# senseBox-MCU_v12.net
KiCad netlist of a schematic drawn in EAGLE
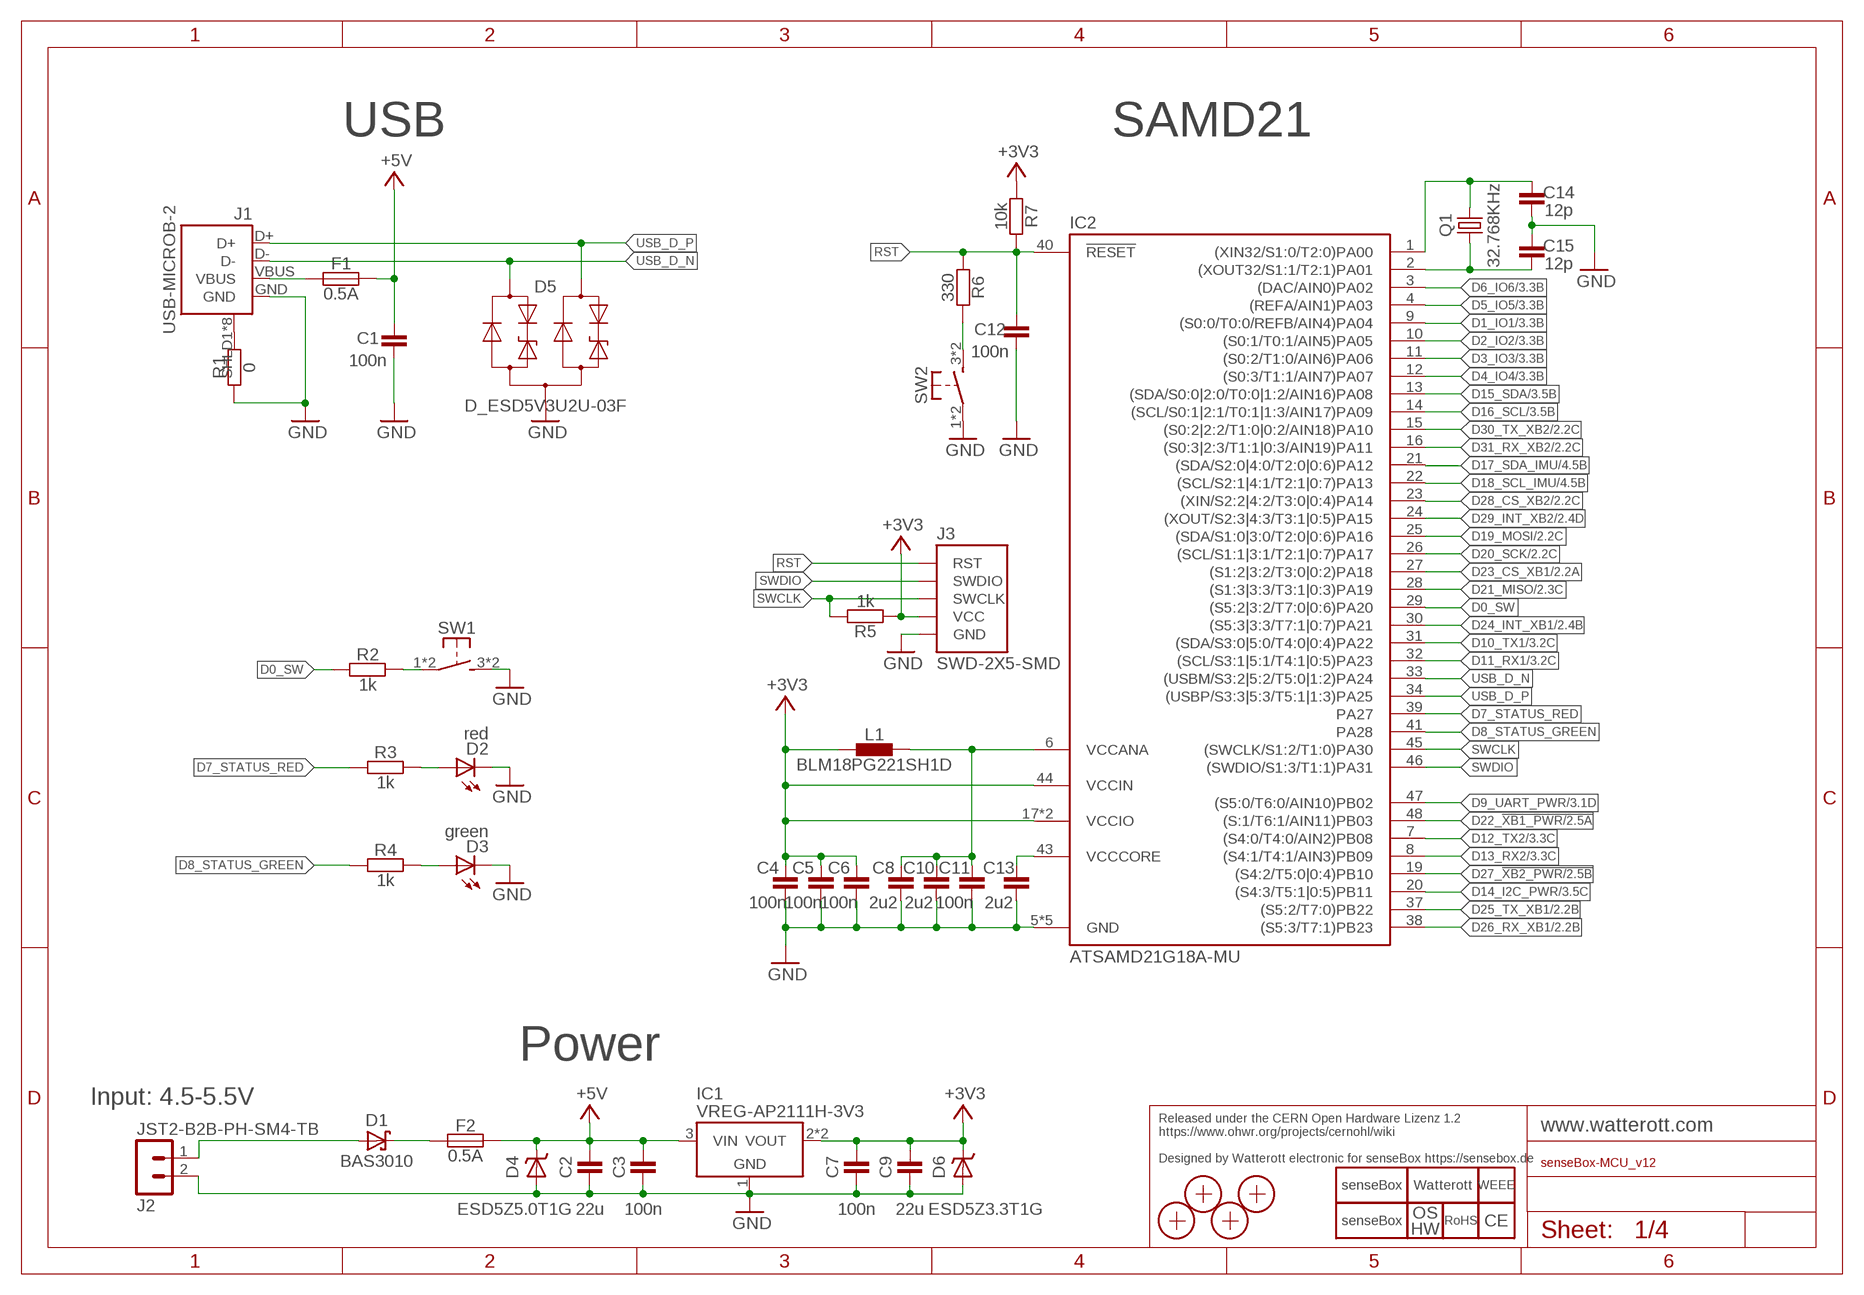
[diagram p0: schematic, sheet 1]
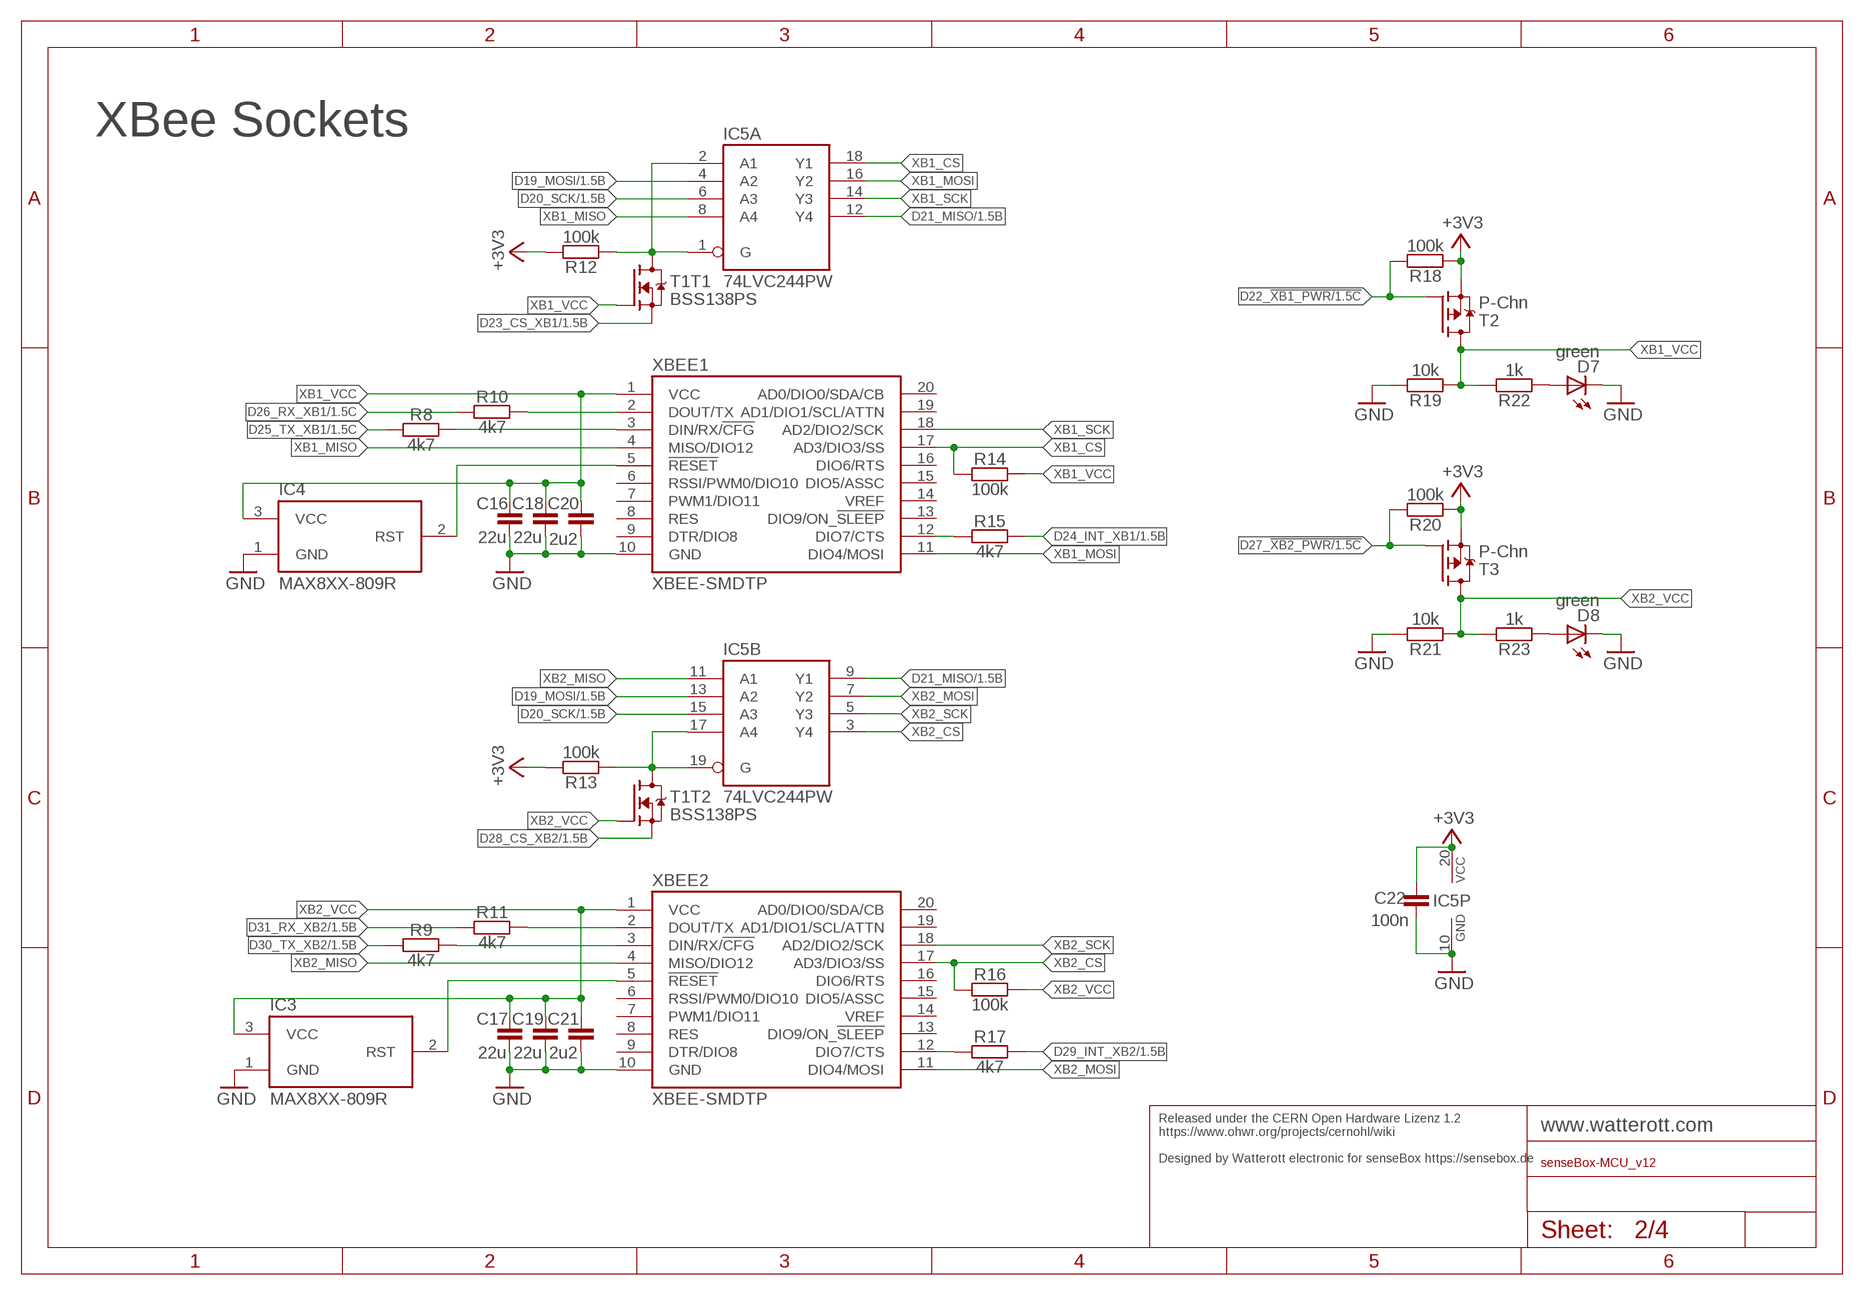
[diagram p1: schematic, sheet 2]
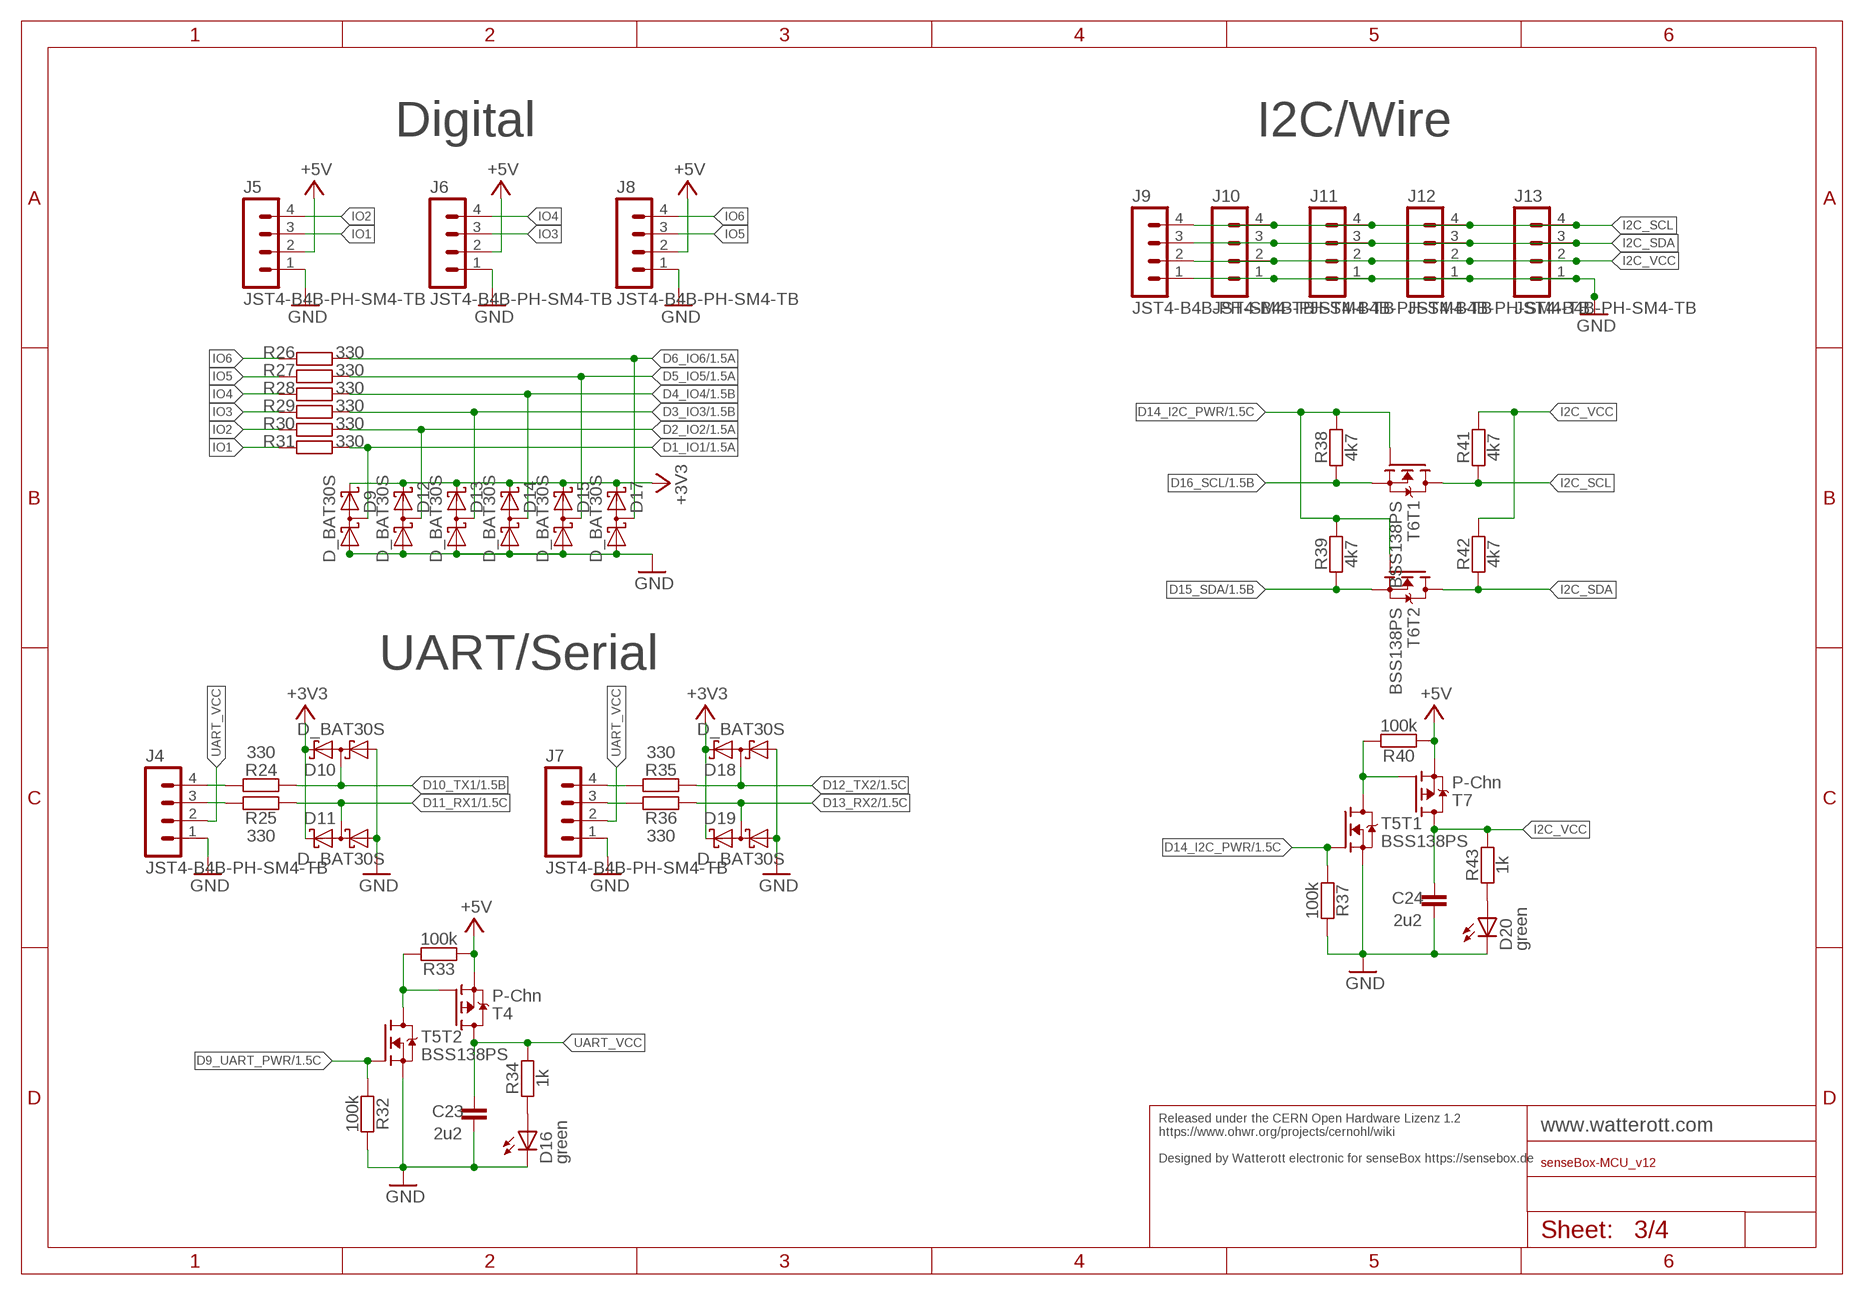
[diagram p2: schematic, sheet 3]
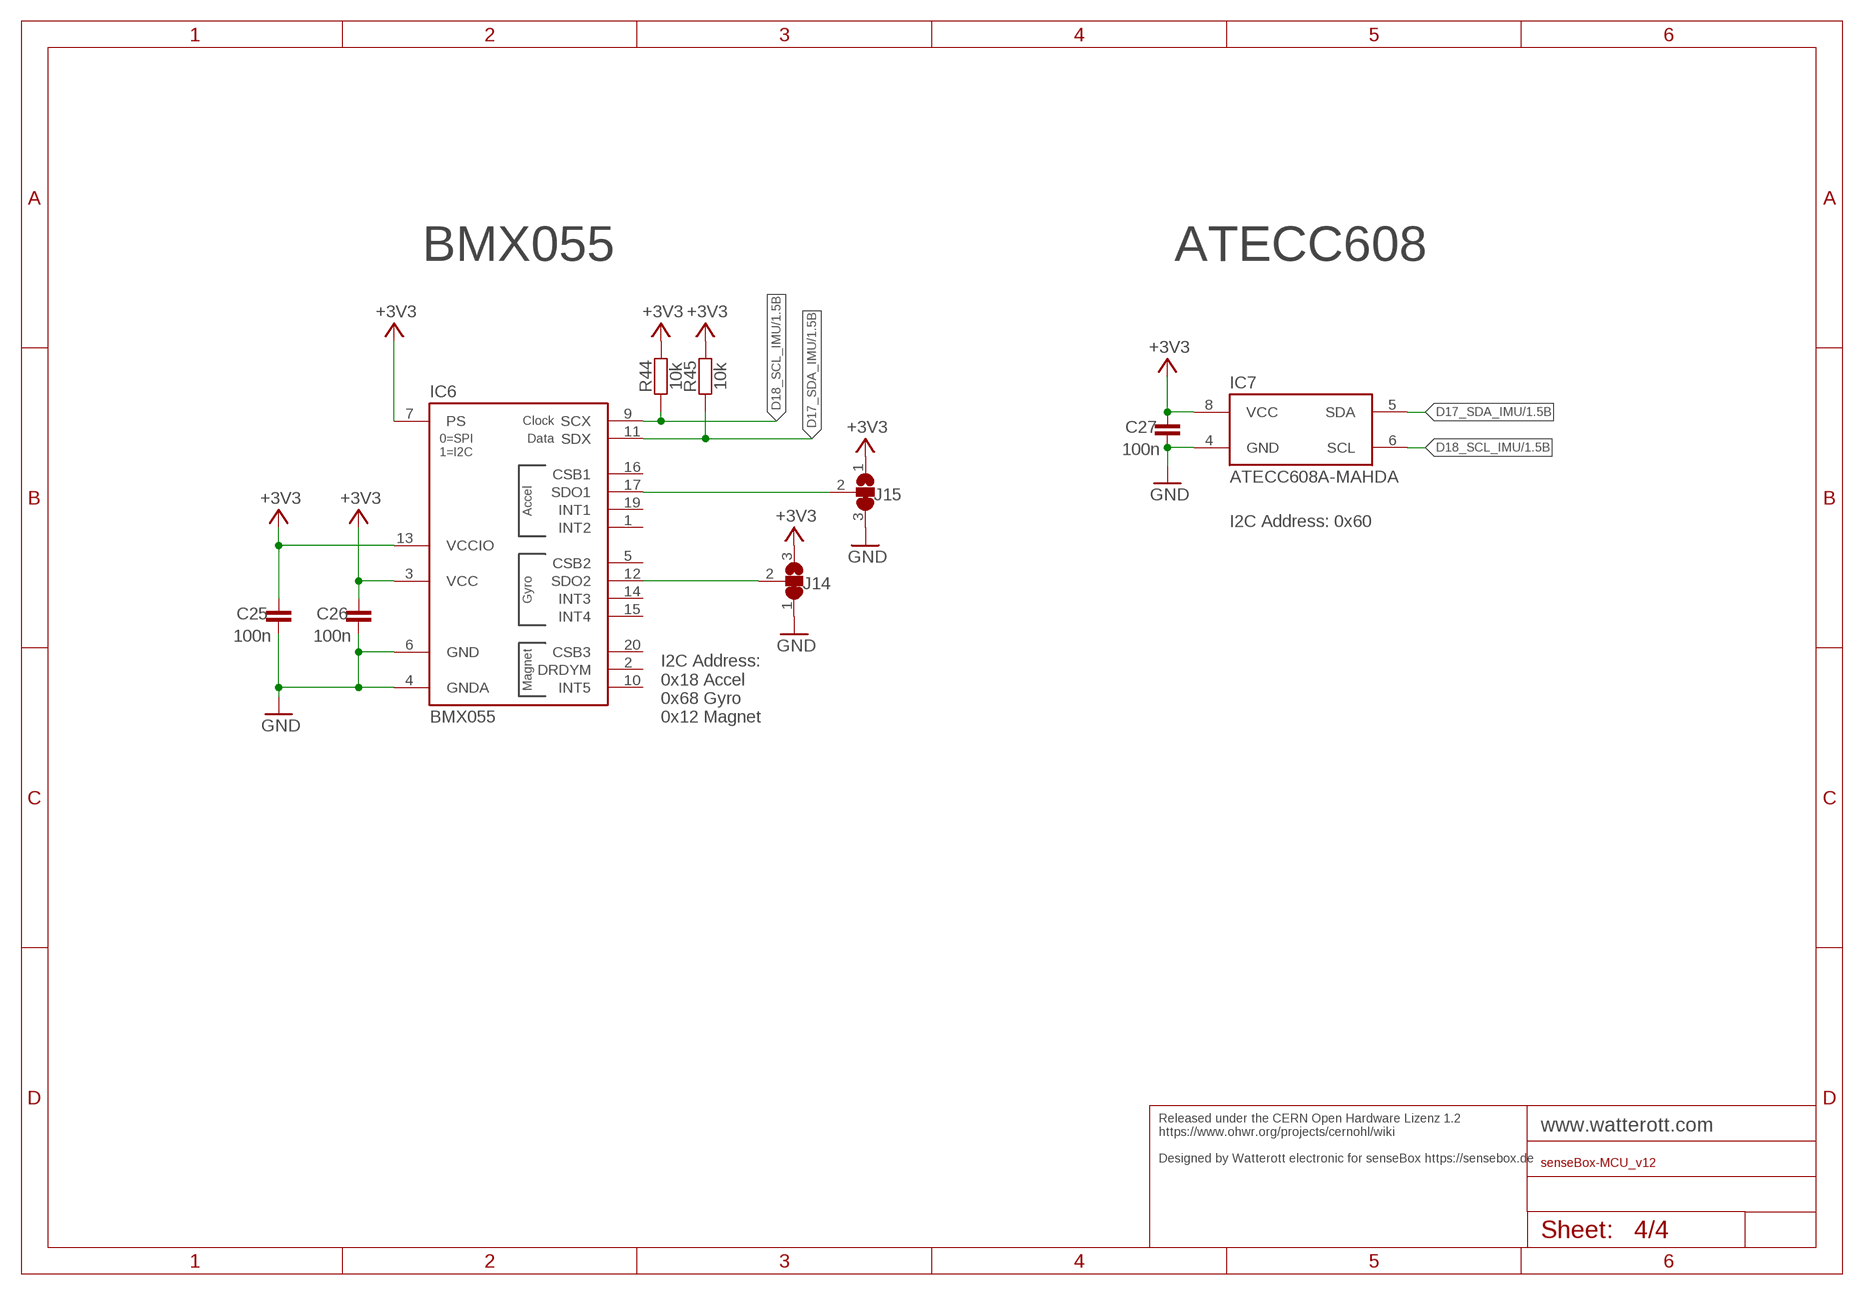
[diagram p3: schematic, sheet 4]

(export (version "E")
  (design (tool "Eeschema 10.0.6"))
  (components
    (comp (ref "C23")
      (value "2u2")
      (footprint "eagle-import:C0402")
      (libsource (lib "eagle-import") (part "CAPACITOR-0402"))
    )
    (comp (ref "C24")
      (value "2u2")
      (footprint "eagle-import:C0402")
      (libsource (lib "eagle-import") (part "CAPACITOR-0402"))
    )
    (comp (ref "D9")
      (value "D_BAT30S")
      (footprint "eagle-import:SOT323")
      (libsource (lib "eagle-import") (part "D_BAT30S"))
    )
    (comp (ref "D10")
      (value "D_BAT30S")
      (footprint "eagle-import:SOT323")
      (libsource (lib "eagle-import") (part "D_BAT30S"))
    )
    (comp (ref "D11")
      (value "D_BAT30S")
      (footprint "eagle-import:SOT323")
      (libsource (lib "eagle-import") (part "D_BAT30S"))
    )
    (comp (ref "D12")
      (value "D_BAT30S")
      (footprint "eagle-import:SOT323")
      (libsource (lib "eagle-import") (part "D_BAT30S"))
    )
    (comp (ref "D13")
      (value "D_BAT30S")
      (footprint "eagle-import:SOT323")
      (libsource (lib "eagle-import") (part "D_BAT30S"))
    )
    (comp (ref "D14")
      (value "D_BAT30S")
      (footprint "eagle-import:SOT323")
      (libsource (lib "eagle-import") (part "D_BAT30S"))
    )
    (comp (ref "D15")
      (value "D_BAT30S")
      (footprint "eagle-import:SOT323")
      (libsource (lib "eagle-import") (part "D_BAT30S"))
    )
    (comp (ref "D16")
      (value "green")
      (footprint "eagle-import:C0603")
      (libsource (lib "eagle-import") (part "LED-0603"))
    )
    (comp (ref "D17")
      (value "D_BAT30S")
      (footprint "eagle-import:SOT323")
      (libsource (lib "eagle-import") (part "D_BAT30S"))
    )
    (comp (ref "D18")
      (value "D_BAT30S")
      (footprint "eagle-import:SOT323")
      (libsource (lib "eagle-import") (part "D_BAT30S"))
    )
    (comp (ref "D19")
      (value "D_BAT30S")
      (footprint "eagle-import:SOT323")
      (libsource (lib "eagle-import") (part "D_BAT30S"))
    )
    (comp (ref "D20")
      (value "green")
      (footprint "eagle-import:C0603")
      (libsource (lib "eagle-import") (part "LED-0603"))
    )
    (comp (ref "J4")
      (value "JST4-B4B-PH-SM4-TB")
      (footprint "eagle-import:JST_B4B-PH-SM4-TB")
      (libsource (lib "eagle-import") (part "JST4-B4B-PH-SM4-TB"))
    )
    (comp (ref "J5")
      (value "JST4-B4B-PH-SM4-TB")
      (footprint "eagle-import:JST_B4B-PH-SM4-TB")
      (libsource (lib "eagle-import") (part "JST4-B4B-PH-SM4-TB"))
    )
    (comp (ref "J6")
      (value "JST4-B4B-PH-SM4-TB")
      (footprint "eagle-import:JST_B4B-PH-SM4-TB")
      (libsource (lib "eagle-import") (part "JST4-B4B-PH-SM4-TB"))
    )
    (comp (ref "J7")
      (value "JST4-B4B-PH-SM4-TB")
      (footprint "eagle-import:JST_B4B-PH-SM4-TB")
      (libsource (lib "eagle-import") (part "JST4-B4B-PH-SM4-TB"))
    )
    (comp (ref "J8")
      (value "JST4-B4B-PH-SM4-TB")
      (footprint "eagle-import:JST_B4B-PH-SM4-TB")
      (libsource (lib "eagle-import") (part "JST4-B4B-PH-SM4-TB"))
    )
    (comp (ref "J9")
      (value "JST4-B4B-PH-SM4-TB")
      (footprint "eagle-import:JST_B4B-PH-SM4-TB")
      (libsource (lib "eagle-import") (part "JST4-B4B-PH-SM4-TB"))
    )
    (comp (ref "J10")
      (value "JST4-B4B-PH-SM4-TB")
      (footprint "eagle-import:JST_B4B-PH-SM4-TB")
      (libsource (lib "eagle-import") (part "JST4-B4B-PH-SM4-TB"))
    )
    (comp (ref "J11")
      (value "JST4-B4B-PH-SM4-TB")
      (footprint "eagle-import:JST_B4B-PH-SM4-TB")
      (libsource (lib "eagle-import") (part "JST4-B4B-PH-SM4-TB"))
    )
    (comp (ref "J12")
      (value "JST4-B4B-PH-SM4-TB")
      (footprint "eagle-import:JST_B4B-PH-SM4-TB")
      (libsource (lib "eagle-import") (part "JST4-B4B-PH-SM4-TB"))
    )
    (comp (ref "J13")
      (value "JST4-B4B-PH-SM4-TB")
      (footprint "eagle-import:JST_B4B-PH-SM4-TB")
      (libsource (lib "eagle-import") (part "JST4-B4B-PH-SM4-TB"))
    )
    (comp (ref "R24")
      (value "330")
      (footprint "eagle-import:C0402")
      (libsource (lib "eagle-import") (part "RESISTOR-0402"))
    )
    (comp (ref "R25")
      (value "330")
      (footprint "eagle-import:C0402")
      (libsource (lib "eagle-import") (part "RESISTOR-0402"))
    )
    (comp (ref "R26")
      (value "330")
      (footprint "eagle-import:C0402")
      (libsource (lib "eagle-import") (part "RESISTOR-0402"))
    )
    (comp (ref "R27")
      (value "330")
      (footprint "eagle-import:C0402")
      (libsource (lib "eagle-import") (part "RESISTOR-0402"))
    )
    (comp (ref "R28")
      (value "330")
      (footprint "eagle-import:C0402")
      (libsource (lib "eagle-import") (part "RESISTOR-0402"))
    )
    (comp (ref "R29")
      (value "330")
      (footprint "eagle-import:C0402")
      (libsource (lib "eagle-import") (part "RESISTOR-0402"))
    )
    (comp (ref "R30")
      (value "330")
      (footprint "eagle-import:C0402")
      (libsource (lib "eagle-import") (part "RESISTOR-0402"))
    )
    (comp (ref "R31")
      (value "330")
      (footprint "eagle-import:C0402")
      (libsource (lib "eagle-import") (part "RESISTOR-0402"))
    )
    (comp (ref "R32")
      (value "100k")
      (footprint "eagle-import:C0402")
      (libsource (lib "eagle-import") (part "RESISTOR-0402"))
    )
    (comp (ref "R33")
      (value "100k")
      (footprint "eagle-import:C0402")
      (libsource (lib "eagle-import") (part "RESISTOR-0402"))
    )
    (comp (ref "R34")
      (value "1k")
      (footprint "eagle-import:C0402")
      (libsource (lib "eagle-import") (part "RESISTOR-0402"))
    )
    (comp (ref "R35")
      (value "330")
      (footprint "eagle-import:C0402")
      (libsource (lib "eagle-import") (part "RESISTOR-0402"))
    )
    (comp (ref "R36")
      (value "330")
      (footprint "eagle-import:C0402")
      (libsource (lib "eagle-import") (part "RESISTOR-0402"))
    )
    (comp (ref "R37")
      (value "100k")
      (footprint "eagle-import:C0402")
      (libsource (lib "eagle-import") (part "RESISTOR-0402"))
    )
    (comp (ref "R38")
      (value "4k7")
      (footprint "eagle-import:C0402")
      (libsource (lib "eagle-import") (part "RESISTOR-0402"))
    )
    (comp (ref "R39")
      (value "4k7")
      (footprint "eagle-import:C0402")
      (libsource (lib "eagle-import") (part "RESISTOR-0402"))
    )
    (comp (ref "R40")
      (value "100k")
      (footprint "eagle-import:C0402")
      (libsource (lib "eagle-import") (part "RESISTOR-0402"))
    )
    (comp (ref "R41")
      (value "4k7")
      (footprint "eagle-import:C0402")
      (libsource (lib "eagle-import") (part "RESISTOR-0402"))
    )
    (comp (ref "R42")
      (value "4k7")
      (footprint "eagle-import:C0402")
      (libsource (lib "eagle-import") (part "RESISTOR-0402"))
    )
    (comp (ref "R43")
      (value "1k")
      (footprint "eagle-import:C0402")
      (libsource (lib "eagle-import") (part "RESISTOR-0402"))
    )
    (comp (ref "T4")
      (value "P-Chn")
      (footprint "eagle-import:SOT23")
      (libsource (lib "eagle-import") (part "MOSFET-P-SOT23"))
    )
    (comp (ref "T5")
      (value "BSS138PS")
      (footprint "eagle-import:SOT363")
      (libsource (lib "eagle-import") (part "BSS138PS"))
    )
    (comp (ref "T6")
      (value "BSS138PS")
      (footprint "eagle-import:SOT363")
      (libsource (lib "eagle-import") (part "BSS138PS"))
    )
    (comp (ref "T7")
      (value "P-Chn")
      (footprint "eagle-import:SOT23")
      (libsource (lib "eagle-import") (part "MOSFET-P-SOT23"))
    )
    (comp (ref "C1")
      (value "100n")
      (footprint "eagle-import:C0402")
      (libsource (lib "eagle-import") (part "CAPACITOR-0402"))
    )
    (comp (ref "C2")
      (value "22u")
      (footprint "eagle-import:C0805")
      (libsource (lib "eagle-import") (part "CAPACITOR-0805"))
    )
    (comp (ref "C3")
      (value "100n")
      (footprint "eagle-import:C0402")
      (libsource (lib "eagle-import") (part "CAPACITOR-0402"))
    )
    (comp (ref "C4")
      (value "100n")
      (footprint "eagle-import:C0402")
      (libsource (lib "eagle-import") (part "CAPACITOR-0402"))
    )
    (comp (ref "C5")
      (value "100n")
      (footprint "eagle-import:C0402")
      (libsource (lib "eagle-import") (part "CAPACITOR-0402"))
    )
    (comp (ref "C6")
      (value "100n")
      (footprint "eagle-import:C0402")
      (libsource (lib "eagle-import") (part "CAPACITOR-0402"))
    )
    (comp (ref "C7")
      (value "100n")
      (footprint "eagle-import:C0402")
      (libsource (lib "eagle-import") (part "CAPACITOR-0402"))
    )
    (comp (ref "C8")
      (value "2u2")
      (footprint "eagle-import:C0402")
      (libsource (lib "eagle-import") (part "CAPACITOR-0402"))
    )
    (comp (ref "C9")
      (value "22u")
      (footprint "eagle-import:C0805")
      (libsource (lib "eagle-import") (part "CAPACITOR-0805"))
    )
    (comp (ref "C10")
      (value "2u2")
      (footprint "eagle-import:C0402")
      (libsource (lib "eagle-import") (part "CAPACITOR-0402"))
    )
    (comp (ref "C11")
      (value "100n")
      (footprint "eagle-import:C0402")
      (libsource (lib "eagle-import") (part "CAPACITOR-0402"))
    )
    (comp (ref "C12")
      (value "100n")
      (footprint "eagle-import:C0402")
      (libsource (lib "eagle-import") (part "CAPACITOR-0402"))
    )
    (comp (ref "C13")
      (value "2u2")
      (footprint "eagle-import:C0402")
      (libsource (lib "eagle-import") (part "CAPACITOR-0402"))
    )
    (comp (ref "C14")
      (value "12p")
      (footprint "eagle-import:C0402")
      (libsource (lib "eagle-import") (part "CAPACITOR-0402"))
    )
    (comp (ref "C15")
      (value "12p")
      (footprint "eagle-import:C0402")
      (libsource (lib "eagle-import") (part "CAPACITOR-0402"))
    )
    (comp (ref "D1")
      (value "BAS3010")
      (footprint "eagle-import:SOD323")
      (libsource (lib "eagle-import") (part "D_SCHOTTKY-SOD323"))
    )
    (comp (ref "D2")
      (value "red")
      (footprint "eagle-import:C0603")
      (libsource (lib "eagle-import") (part "LED-0603"))
    )
    (comp (ref "D3")
      (value "green")
      (footprint "eagle-import:C0603")
      (libsource (lib "eagle-import") (part "LED-0603"))
    )
    (comp (ref "D4")
      (value "ESD5Z5.0T1G")
      (footprint "eagle-import:SOD523")
      (libsource (lib "eagle-import") (part "D_TVS-SOD523"))
    )
    (comp (ref "D5")
      (value "D_ESD5V3U2U-03F")
      (footprint "eagle-import:SOT723")
      (libsource (lib "eagle-import") (part "D_ESD5V3U2U-03F"))
    )
    (comp (ref "D6")
      (value "ESD5Z3.3T1G")
      (footprint "eagle-import:SOD523")
      (libsource (lib "eagle-import") (part "D_TVS-SOD523"))
    )
    (comp (ref "F1")
      (value "0.5A")
      (footprint "eagle-import:C0805")
      (libsource (lib "eagle-import") (part "FUSE-0805"))
    )
    (comp (ref "F2")
      (value "0.5A")
      (footprint "eagle-import:C0805")
      (libsource (lib "eagle-import") (part "FUSE-0805"))
    )
    (comp (ref "IC1")
      (value "VREG-AP2111H-3V3")
      (footprint "eagle-import:SOT223")
      (libsource (lib "eagle-import") (part "VREG-TS1117CW-3V3"))
    )
    (comp (ref "IC2")
      (value "ATSAMD21G18A-MU")
      (footprint "eagle-import:QFN48-PAD")
      (libsource (lib "eagle-import") (part "ATSAMD21G18A-MU"))
    )
    (comp (ref "J1")
      (value "USB-MICROB-2")
      (footprint "eagle-import:USB-MICROB-10118194")
      (libsource (lib "eagle-import") (part "USB-MICROB-2"))
    )
    (comp (ref "J2")
      (value "JST2-B2B-PH-SM4-TB")
      (footprint "eagle-import:JST_B2B-PH-SM4-TB")
      (libsource (lib "eagle-import") (part "JST2-B2B-PH-SM4-TB"))
    )
    (comp (ref "J3")
      (value "SWD-2X5-SMD")
      (footprint "eagle-import:SWD-2X5_SMD")
      (libsource (lib "eagle-import") (part "SWD-2X5-SMD"))
    )
    (comp (ref "L1")
      (value "BLM18PG221SH1D")
      (footprint "eagle-import:C0603")
      (libsource (lib "eagle-import") (part "INDUCTOR-0603"))
    )
    (comp (ref "LOGO1")
      (value "LOGO_SENSEBOX-12")
      (footprint "eagle-import:SB_12MM")
      (libsource (lib "eagle-import") (part "LOGO_SENSEBOX-12"))
    )
    (comp (ref "LOGO2")
      (value "LOGO_SENSEBOX-QR")
      (footprint "eagle-import:SB-QR_20MM")
      (libsource (lib "eagle-import") (part "LOGO_SENSEBOX-QR"))
    )
    (comp (ref "LOGO3")
      (value "OSHW_LOGOX0070")
      (footprint "eagle-import:OSHW_3MM")
      (libsource (lib "eagle-import") (part "LOGO_OSHW-3"))
    )
    (comp (ref "LOGO4")
      (value "LOGO_SPARK-4")
      (footprint "eagle-import:SPARK_4MM")
      (libsource (lib "eagle-import") (part "LOGO_SPARK-4"))
    )
    (comp (ref "LOGO5")
      (value "LOGO_ROHS-4")
      (footprint "eagle-import:ROHS_4MM")
      (libsource (lib "eagle-import") (part "LOGO_ROHS-4"))
    )
    (comp (ref "LOGO6")
      (value "LOGO_WEEE-4")
      (footprint "eagle-import:WEEE_4MM")
      (libsource (lib "eagle-import") (part "LOGO_WEEE-4"))
    )
    (comp (ref "LOGO7")
      (value "LOGO_CE-4")
      (footprint "eagle-import:CE_4MM")
      (libsource (lib "eagle-import") (part "LOGO_CE-4"))
    )
    (comp (ref "Q1")
      (value "32.768KHz")
      (footprint "eagle-import:CRYSTAL_ZM315")
      (libsource (lib "eagle-import") (part "CRYSTAL-ZM315"))
    )
    (comp (ref "R1")
      (value "0")
      (footprint "eagle-import:C0402")
      (libsource (lib "eagle-import") (part "RESISTOR-0402"))
    )
    (comp (ref "R2")
      (value "1k")
      (footprint "eagle-import:C0402")
      (libsource (lib "eagle-import") (part "RESISTOR-0402"))
    )
    (comp (ref "R3")
      (value "1k")
      (footprint "eagle-import:C0402")
      (libsource (lib "eagle-import") (part "RESISTOR-0402"))
    )
    (comp (ref "R4")
      (value "1k")
      (footprint "eagle-import:C0402")
      (libsource (lib "eagle-import") (part "RESISTOR-0402"))
    )
    (comp (ref "R5")
      (value "1k")
      (footprint "eagle-import:C0402")
      (libsource (lib "eagle-import") (part "RESISTOR-0402"))
    )
    (comp (ref "R6")
      (value "330")
      (footprint "eagle-import:C0402")
      (libsource (lib "eagle-import") (part "RESISTOR-0402"))
    )
    (comp (ref "R7")
      (value "10k")
      (footprint "eagle-import:C0402")
      (libsource (lib "eagle-import") (part "RESISTOR-0402"))
    )
    (comp (ref "SW1")
      (value "PTS645SH50SMTR92-Grey")
      (footprint "eagle-import:SW6X6_SMD")
      (libsource (lib "eagle-import") (part "SW-TACTILE-6X6_SMD"))
    )
    (comp (ref "SW2")
      (value "PTS645SK50SMTR92-Red")
      (footprint "eagle-import:SW6X6_SMD")
      (libsource (lib "eagle-import") (part "SW-TACTILE-6X6_SMD"))
    )
    (comp (ref "X1")
      (value "PASSER-07")
      (footprint "eagle-import:PASSER_07MM")
      (libsource (lib "eagle-import") (part "PASSER-07"))
    )
    (comp (ref "X2")
      (value "PASSER-07")
      (footprint "eagle-import:PASSER_07MM")
      (libsource (lib "eagle-import") (part "PASSER-07"))
    )
    (comp (ref "X3")
      (value "PASSER-07")
      (footprint "eagle-import:PASSER_07MM")
      (libsource (lib "eagle-import") (part "PASSER-07"))
    )
    (comp (ref "X4")
      (value "PASSER-07")
      (footprint "eagle-import:PASSER_07MM")
      (libsource (lib "eagle-import") (part "PASSER-07"))
    )
    (comp (ref "C25")
      (value "100n")
      (footprint "eagle-import:C0402")
      (libsource (lib "eagle-import") (part "CAPACITOR-0402"))
    )
    (comp (ref "C26")
      (value "100n")
      (footprint "eagle-import:C0402")
      (libsource (lib "eagle-import") (part "CAPACITOR-0402"))
    )
    (comp (ref "C27")
      (value "100n")
      (footprint "eagle-import:C0402")
      (libsource (lib "eagle-import") (part "CAPACITOR-0402"))
    )
    (comp (ref "IC6")
      (value "BMX055")
      (footprint "eagle-import:BMX055")
      (libsource (lib "eagle-import") (part "BMX055"))
    )
    (comp (ref "IC7")
      (value "ATECC608A-MAHDA")
      (footprint "eagle-import:UDFN8")
      (libsource (lib "eagle-import") (part "ATECC608A-MAHDA"))
    )
    (comp (ref "J14")
      (value "JUMPER3-0402")
      (footprint "eagle-import:JUMPER3-0402")
      (libsource (lib "eagle-import") (part "JUMPER3-0402"))
    )
    (comp (ref "J15")
      (value "JUMPER3-0402")
      (footprint "eagle-import:JUMPER3-0402")
      (libsource (lib "eagle-import") (part "JUMPER3-0402"))
    )
    (comp (ref "R44")
      (value "10k")
      (footprint "eagle-import:C0402")
      (libsource (lib "eagle-import") (part "RESISTOR-0402"))
    )
    (comp (ref "R45")
      (value "10k")
      (footprint "eagle-import:C0402")
      (libsource (lib "eagle-import") (part "RESISTOR-0402"))
    )
    (comp (ref "C16")
      (value "22u")
      (footprint "eagle-import:C0805")
      (libsource (lib "eagle-import") (part "CAPACITOR-0805"))
    )
    (comp (ref "C17")
      (value "22u")
      (footprint "eagle-import:C0805")
      (libsource (lib "eagle-import") (part "CAPACITOR-0805"))
    )
    (comp (ref "C18")
      (value "22u")
      (footprint "eagle-import:C0805")
      (libsource (lib "eagle-import") (part "CAPACITOR-0805"))
    )
    (comp (ref "C19")
      (value "22u")
      (footprint "eagle-import:C0805")
      (libsource (lib "eagle-import") (part "CAPACITOR-0805"))
    )
    (comp (ref "C20")
      (value "2u2")
      (footprint "eagle-import:C0402")
      (libsource (lib "eagle-import") (part "CAPACITOR-0402"))
    )
    (comp (ref "C21")
      (value "2u2")
      (footprint "eagle-import:C0402")
      (libsource (lib "eagle-import") (part "CAPACITOR-0402"))
    )
    (comp (ref "C22")
      (value "100n")
      (footprint "eagle-import:C0402")
      (libsource (lib "eagle-import") (part "CAPACITOR-0402"))
    )
    (comp (ref "D7")
      (value "green")
      (footprint "eagle-import:C0603")
      (libsource (lib "eagle-import") (part "LED-0603"))
    )
    (comp (ref "D8")
      (value "green")
      (footprint "eagle-import:C0603")
      (libsource (lib "eagle-import") (part "LED-0603"))
    )
    (comp (ref "IC3")
      (value "MAX8XX-809R")
      (footprint "eagle-import:SOT23")
      (libsource (lib "eagle-import") (part "MAX8XX-809R"))
    )
    (comp (ref "IC4")
      (value "MAX8XX-809R")
      (footprint "eagle-import:SOT23")
      (libsource (lib "eagle-import") (part "MAX8XX-809R"))
    )
    (comp (ref "IC5")
      (value "74LVC244PW")
      (footprint "eagle-import:TSSOP20")
      (libsource (lib "eagle-import") (part "74244PWLVC"))
    )
    (comp (ref "R8")
      (value "4k7")
      (footprint "eagle-import:C0402")
      (libsource (lib "eagle-import") (part "RESISTOR-0402"))
    )
    (comp (ref "R9")
      (value "4k7")
      (footprint "eagle-import:C0402")
      (libsource (lib "eagle-import") (part "RESISTOR-0402"))
    )
    (comp (ref "R10")
      (value "4k7")
      (footprint "eagle-import:C0402")
      (libsource (lib "eagle-import") (part "RESISTOR-0402"))
    )
    (comp (ref "R11")
      (value "4k7")
      (footprint "eagle-import:C0402")
      (libsource (lib "eagle-import") (part "RESISTOR-0402"))
    )
    (comp (ref "R12")
      (value "100k")
      (footprint "eagle-import:C0402")
      (libsource (lib "eagle-import") (part "RESISTOR-0402"))
    )
    (comp (ref "R13")
      (value "100k")
      (footprint "eagle-import:C0402")
      (libsource (lib "eagle-import") (part "RESISTOR-0402"))
    )
    (comp (ref "R14")
      (value "100k")
      (footprint "eagle-import:C0402")
      (libsource (lib "eagle-import") (part "RESISTOR-0402"))
    )
    (comp (ref "R15")
      (value "4k7")
      (footprint "eagle-import:C0402")
      (libsource (lib "eagle-import") (part "RESISTOR-0402"))
    )
    (comp (ref "R16")
      (value "100k")
      (footprint "eagle-import:C0402")
      (libsource (lib "eagle-import") (part "RESISTOR-0402"))
    )
    (comp (ref "R17")
      (value "4k7")
      (footprint "eagle-import:C0402")
      (libsource (lib "eagle-import") (part "RESISTOR-0402"))
    )
    (comp (ref "R18")
      (value "100k")
      (footprint "eagle-import:C0402")
      (libsource (lib "eagle-import") (part "RESISTOR-0402"))
    )
    (comp (ref "R19")
      (value "10k")
      (footprint "eagle-import:C0402")
      (libsource (lib "eagle-import") (part "RESISTOR-0402"))
    )
    (comp (ref "R20")
      (value "100k")
      (footprint "eagle-import:C0402")
      (libsource (lib "eagle-import") (part "RESISTOR-0402"))
    )
    (comp (ref "R21")
      (value "10k")
      (footprint "eagle-import:C0402")
      (libsource (lib "eagle-import") (part "RESISTOR-0402"))
    )
    (comp (ref "R22")
      (value "1k")
      (footprint "eagle-import:C0402")
      (libsource (lib "eagle-import") (part "RESISTOR-0402"))
    )
    (comp (ref "R23")
      (value "1k")
      (footprint "eagle-import:C0402")
      (libsource (lib "eagle-import") (part "RESISTOR-0402"))
    )
    (comp (ref "T1")
      (value "BSS138PS")
      (footprint "eagle-import:SOT363")
      (libsource (lib "eagle-import") (part "BSS138PS"))
    )
    (comp (ref "T2")
      (value "P-Chn")
      (footprint "eagle-import:SOT23")
      (libsource (lib "eagle-import") (part "MOSFET-P-SOT23"))
    )
    (comp (ref "T3")
      (value "P-Chn")
      (footprint "eagle-import:SOT23")
      (libsource (lib "eagle-import") (part "MOSFET-P-SOT23"))
    )
    (comp (ref "XBEE1")
      (value "XBEE-SMDTP")
      (footprint "eagle-import:XBEE_SMD_TP")
      (libsource (lib "eagle-import") (part "XBEE-SMDTP"))
    )
    (comp (ref "XBEE2")
      (value "XBEE-SMDTP")
      (footprint "eagle-import:XBEE_SMD_TP")
      (libsource (lib "eagle-import") (part "XBEE-SMDTP"))
    )
  )
  (nets
    (net (code "1") (name "+3V3") (class "Default")
      (node (ref "C22") (pin "2") (pinfunction "2_2") (pintype "passive"))
      (node (ref "C25") (pin "2") (pinfunction "2_2") (pintype "passive"))
      (node (ref "C26") (pin "2") (pinfunction "2_2") (pintype "passive"))
      (node (ref "C27") (pin "2") (pinfunction "2_2") (pintype "passive"))
      (node (ref "C4") (pin "2") (pinfunction "2_2") (pintype "passive"))
      (node (ref "C5") (pin "2") (pinfunction "2_2") (pintype "passive"))
      (node (ref "C6") (pin "2") (pinfunction "2_2") (pintype "passive"))
      (node (ref "C7") (pin "2") (pinfunction "2_2") (pintype "passive"))
      (node (ref "C9") (pin "2") (pinfunction "2_2") (pintype "passive"))
      (node (ref "D10") (pin "2") (pinfunction "C_2") (pintype "passive"))
      (node (ref "D11") (pin "2") (pinfunction "C_2") (pintype "passive"))
      (node (ref "D12") (pin "2") (pinfunction "C_2") (pintype "passive"))
      (node (ref "D13") (pin "2") (pinfunction "C_2") (pintype "passive"))
      (node (ref "D14") (pin "2") (pinfunction "C_2") (pintype "passive"))
      (node (ref "D15") (pin "2") (pinfunction "C_2") (pintype "passive"))
      (node (ref "D17") (pin "2") (pinfunction "C_2") (pintype "passive"))
      (node (ref "D18") (pin "2") (pinfunction "C_2") (pintype "passive"))
      (node (ref "D19") (pin "2") (pinfunction "C_2") (pintype "passive"))
      (node (ref "D6") (pin "C") (pinfunction "C_C") (pintype "passive"))
      (node (ref "D9") (pin "2") (pinfunction "C_2") (pintype "passive"))
      (node (ref "IC1") (pin "2") (pinfunction "VOUT_2") (pintype "power_in"))
      (node (ref "IC1") (pin "4") (pinfunction "VOUT_4") (pintype "power_in"))
      (node (ref "IC2") (pin "17") (pinfunction "VCCIO_17") (pintype "power_in"))
      (node (ref "IC2") (pin "36") (pinfunction "VCCIO_36") (pintype "power_in"))
      (node (ref "IC2") (pin "44") (pinfunction "VCCIN_44") (pintype "power_in"))
      (node (ref "IC5") (pin "20") (pinfunction "VCC_20") (pintype "power_in"))
      (node (ref "IC6") (pin "13") (pinfunction "VCCIO_13") (pintype "power_in"))
      (node (ref "IC6") (pin "3") (pinfunction "VCC_3") (pintype "power_in"))
      (node (ref "IC6") (pin "7") (pinfunction "PS_7") (pintype "input"))
      (node (ref "IC7") (pin "8") (pinfunction "VCC_8") (pintype "power_in"))
      (node (ref "J14") (pin "3") (pinfunction "3_3") (pintype "passive"))
      (node (ref "J15") (pin "1") (pinfunction "1_1") (pintype "passive"))
      (node (ref "J3") (pin "VCC") (pinfunction "VCC_VCC") (pintype "power_in"))
      (node (ref "L1") (pin "1") (pinfunction "1_1") (pintype "passive"))
      (node (ref "R12") (pin "2") (pinfunction "2_2") (pintype "passive"))
      (node (ref "R13") (pin "2") (pinfunction "2_2") (pintype "passive"))
      (node (ref "R18") (pin "1") (pinfunction "1_1") (pintype "passive"))
      (node (ref "R20") (pin "1") (pinfunction "1_1") (pintype "passive"))
      (node (ref "R44") (pin "2") (pinfunction "2_2") (pintype "passive"))
      (node (ref "R45") (pin "2") (pinfunction "2_2") (pintype "passive"))
      (node (ref "R5") (pin "1") (pinfunction "1_1") (pintype "passive"))
      (node (ref "R7") (pin "1") (pinfunction "1_1") (pintype "passive"))
      (node (ref "T2") (pin "2") (pinfunction "S_2") (pintype "passive"))
      (node (ref "T3") (pin "2") (pinfunction "S_2") (pintype "passive"))
    )
    (net (code "2") (name "+5V") (class "Default")
      (node (ref "C1") (pin "2") (pinfunction "2_2") (pintype "passive"))
      (node (ref "C2") (pin "2") (pinfunction "2_2") (pintype "passive"))
      (node (ref "C3") (pin "2") (pinfunction "2_2") (pintype "passive"))
      (node (ref "D4") (pin "C") (pinfunction "C_C") (pintype "passive"))
      (node (ref "F1") (pin "2") (pinfunction "2_2") (pintype "passive"))
      (node (ref "F2") (pin "2") (pinfunction "2_2") (pintype "passive"))
      (node (ref "IC1") (pin "3") (pinfunction "VIN_3") (pintype "power_in"))
      (node (ref "J5") (pin "2") (pinfunction "2_2") (pintype "passive"))
      (node (ref "J6") (pin "2") (pinfunction "2_2") (pintype "passive"))
      (node (ref "J8") (pin "2") (pinfunction "2_2") (pintype "passive"))
      (node (ref "R33") (pin "1") (pinfunction "1_1") (pintype "passive"))
      (node (ref "R40") (pin "1") (pinfunction "1_1") (pintype "passive"))
      (node (ref "T4") (pin "2") (pinfunction "S_2") (pintype "passive"))
      (node (ref "T7") (pin "2") (pinfunction "S_2") (pintype "passive"))
    )
    (net (code "3") (name "D0_SW") (class "Default")
      (node (ref "IC2") (pin "29") (pinfunction "(S5:2|3:2/T7:0|0:6)PA20_29") (pintype "bidirectional"))
      (node (ref "R2") (pin "1") (pinfunction "1_1") (pintype "passive"))
    )
    (net (code "4") (name "D1_IO1") (class "Default")
      (node (ref "D9") (pin "3") (pinfunction "CA_3") (pintype "passive"))
      (node (ref "IC2") (pin "9") (pinfunction "(S0:0/T0:0/REFB/AIN4)PA04_9") (pintype "bidirectional"))
      (node (ref "R31") (pin "1") (pinfunction "1_1") (pintype "passive"))
    )
    (net (code "5") (name "D2_IO2") (class "Default")
      (node (ref "D12") (pin "3") (pinfunction "CA_3") (pintype "passive"))
      (node (ref "IC2") (pin "10") (pinfunction "(S0:1/T0:1/AIN5)PA05_10") (pintype "bidirectional"))
      (node (ref "R30") (pin "1") (pinfunction "1_1") (pintype "passive"))
    )
    (net (code "6") (name "D3_IO3") (class "Default")
      (node (ref "D13") (pin "3") (pinfunction "CA_3") (pintype "passive"))
      (node (ref "IC2") (pin "11") (pinfunction "(S0:2/T1:0/AIN6)PA06_11") (pintype "bidirectional"))
      (node (ref "R29") (pin "1") (pinfunction "1_1") (pintype "passive"))
    )
    (net (code "7") (name "D4_IO4") (class "Default")
      (node (ref "D14") (pin "3") (pinfunction "CA_3") (pintype "passive"))
      (node (ref "IC2") (pin "12") (pinfunction "(S0:3/T1:1/AIN7)PA07_12") (pintype "bidirectional"))
      (node (ref "R28") (pin "1") (pinfunction "1_1") (pintype "passive"))
    )
    (net (code "8") (name "D5_IO5") (class "Default")
      (node (ref "D15") (pin "3") (pinfunction "CA_3") (pintype "passive"))
      (node (ref "IC2") (pin "4") (pinfunction "(REFA/AIN1)PA03_4") (pintype "bidirectional"))
      (node (ref "R27") (pin "1") (pinfunction "1_1") (pintype "passive"))
    )
    (net (code "9") (name "D6_IO6") (class "Default")
      (node (ref "D17") (pin "3") (pinfunction "CA_3") (pintype "passive"))
      (node (ref "IC2") (pin "3") (pinfunction "(DAC/AIN0)PA02_3") (pintype "bidirectional"))
      (node (ref "R26") (pin "1") (pinfunction "1_1") (pintype "passive"))
    )
    (net (code "10") (name "D7_STATUS_RED") (class "Default")
      (node (ref "IC2") (pin "39") (pinfunction "PA27_39") (pintype "bidirectional"))
      (node (ref "R3") (pin "1") (pinfunction "1_1") (pintype "passive"))
    )
    (net (code "11") (name "D8_STATUS_GREEN") (class "Default")
      (node (ref "IC2") (pin "41") (pinfunction "PA28_41") (pintype "bidirectional"))
      (node (ref "R4") (pin "1") (pinfunction "1_1") (pintype "passive"))
    )
    (net (code "12") (name "D9_UART_PWR") (class "Default")
      (node (ref "IC2") (pin "47") (pinfunction "(S5:0/T6:0/AIN10)PB02_47") (pintype "bidirectional"))
      (node (ref "R32") (pin "1") (pinfunction "1_1") (pintype "passive"))
      (node (ref "T5") (pin "5") (pinfunction "G_5") (pintype "passive"))
    )
    (net (code "13") (name "D10_TX1") (class "Default")
      (node (ref "D10") (pin "3") (pinfunction "CA_3") (pintype "passive"))
      (node (ref "IC2") (pin "31") (pinfunction "(SDA/S3:0|5:0/T4:0|0:4)PA22_31") (pintype "bidirectional"))
      (node (ref "R24") (pin "1") (pinfunction "1_1") (pintype "passive"))
    )
    (net (code "14") (name "D11_RX1") (class "Default")
      (node (ref "D11") (pin "3") (pinfunction "CA_3") (pintype "passive"))
      (node (ref "IC2") (pin "32") (pinfunction "(SCL/S3:1|5:1/T4:1|0:5)PA23_32") (pintype "bidirectional"))
      (node (ref "R25") (pin "1") (pinfunction "1_1") (pintype "passive"))
    )
    (net (code "15") (name "D12_TX2") (class "Default")
      (node (ref "D18") (pin "3") (pinfunction "CA_3") (pintype "passive"))
      (node (ref "IC2") (pin "7") (pinfunction "(S4:0/T4:0/AIN2)PB08_7") (pintype "bidirectional"))
      (node (ref "R35") (pin "1") (pinfunction "1_1") (pintype "passive"))
    )
    (net (code "16") (name "D13_RX2") (class "Default")
      (node (ref "D19") (pin "3") (pinfunction "CA_3") (pintype "passive"))
      (node (ref "IC2") (pin "8") (pinfunction "(S4:1/T4:1/AIN3)PB09_8") (pintype "bidirectional"))
      (node (ref "R36") (pin "1") (pinfunction "1_1") (pintype "passive"))
    )
    (net (code "17") (name "D14_I2C_PWR") (class "Default")
      (node (ref "IC2") (pin "20") (pinfunction "(S4:3/T5:1|0:5)PB11_20") (pintype "bidirectional"))
      (node (ref "R37") (pin "1") (pinfunction "1_1") (pintype "passive"))
      (node (ref "R38") (pin "2") (pinfunction "2_2") (pintype "passive"))
      (node (ref "R39") (pin "2") (pinfunction "2_2") (pintype "passive"))
      (node (ref "T5") (pin "2") (pinfunction "G_2") (pintype "passive"))
      (node (ref "T6") (pin "2") (pinfunction "G_2") (pintype "passive"))
      (node (ref "T6") (pin "5") (pinfunction "G_5") (pintype "passive"))
    )
    (net (code "18") (name "D15_SDA") (class "Default")
      (node (ref "IC2") (pin "13") (pinfunction "(SDA/S0:0|2:0/T0:0|1:2/AIN16)PA08_13") (pintype "bidirectional"))
      (node (ref "R39") (pin "1") (pinfunction "1_1") (pintype "passive"))
      (node (ref "T6") (pin "4") (pinfunction "S_4") (pintype "passive"))
    )
    (net (code "19") (name "D16_SCL") (class "Default")
      (node (ref "IC2") (pin "14") (pinfunction "(SCL/S0:1|2:1/T0:1|1:3/AIN17)PA09_14") (pintype "bidirectional"))
      (node (ref "R38") (pin "1") (pinfunction "1_1") (pintype "passive"))
      (node (ref "T6") (pin "1") (pinfunction "S_1") (pintype "passive"))
    )
    (net (code "20") (name "D17_SDA_IMU") (class "Default")
      (node (ref "IC2") (pin "21") (pinfunction "(SDA/S2:0|4:0/T2:0|0:6)PA12_21") (pintype "bidirectional"))
      (node (ref "IC6") (pin "11") (pinfunction "SDX_11") (pintype "bidirectional"))
      (node (ref "IC7") (pin "5") (pinfunction "SDA_5") (pintype "bidirectional"))
      (node (ref "R45") (pin "1") (pinfunction "1_1") (pintype "passive"))
    )
    (net (code "21") (name "D18_SCL_IMU") (class "Default")
      (node (ref "IC2") (pin "22") (pinfunction "(SCL/S2:1|4:1/T2:1|0:7)PA13_22") (pintype "bidirectional"))
      (node (ref "IC6") (pin "9") (pinfunction "SCX_9") (pintype "bidirectional"))
      (node (ref "IC7") (pin "6") (pinfunction "SCL_6") (pintype "bidirectional"))
      (node (ref "R44") (pin "1") (pinfunction "1_1") (pintype "passive"))
    )
    (net (code "22") (name "D19_MOSI") (class "Default")
      (node (ref "IC2") (pin "25") (pinfunction "(SDA/S1:0|3:0/T2:0|0:6)PA16_25") (pintype "bidirectional"))
      (node (ref "IC5") (pin "13") (pinfunction "A2_13") (pintype "input"))
      (node (ref "IC5") (pin "4") (pinfunction "A2_4") (pintype "input"))
    )
    (net (code "23") (name "D20_SCK") (class "Default")
      (node (ref "IC2") (pin "26") (pinfunction "(SCL/S1:1|3:1/T2:1|0:7)PA17_26") (pintype "bidirectional"))
      (node (ref "IC5") (pin "15") (pinfunction "A3_15") (pintype "input"))
      (node (ref "IC5") (pin "6") (pinfunction "A3_6") (pintype "input"))
    )
    (net (code "24") (name "D21_MISO") (class "Default")
      (node (ref "IC2") (pin "28") (pinfunction "(S1:3|3:3/T3:1|0:3)PA19_28") (pintype "bidirectional"))
      (node (ref "IC5") (pin "12") (pinfunction "Y4_12") (pintype "tri_state"))
      (node (ref "IC5") (pin "9") (pinfunction "Y1_9") (pintype "tri_state"))
    )
    (net (code "25") (name "D22_~{XB1_PWR}") (class "Default")
      (node (ref "IC2") (pin "48") (pinfunction "(S:1/T6:1/AIN11)PB03_48") (pintype "bidirectional"))
      (node (ref "R18") (pin "2") (pinfunction "2_2") (pintype "passive"))
      (node (ref "T2") (pin "1") (pinfunction "G_1") (pintype "passive"))
    )
    (net (code "26") (name "D23_CS_XB1") (class "Default")
      (node (ref "IC2") (pin "27") (pinfunction "(S1:2|3:2/T3:0|0:2)PA18_27") (pintype "bidirectional"))
      (node (ref "T1") (pin "1") (pinfunction "S_1") (pintype "passive"))
    )
    (net (code "27") (name "D24_INT_XB1") (class "Default")
      (node (ref "IC2") (pin "30") (pinfunction "(S5:3|3:3/T7:1|0:7)PA21_30") (pintype "bidirectional"))
      (node (ref "R15") (pin "2") (pinfunction "2_2") (pintype "passive"))
    )
    (net (code "28") (name "D25_TX_XB1") (class "Default")
      (node (ref "IC2") (pin "37") (pinfunction "(S5:2/T7:0)PB22_37") (pintype "bidirectional"))
      (node (ref "R8") (pin "1") (pinfunction "1_1") (pintype "passive"))
    )
    (net (code "29") (name "D26_RX_XB1") (class "Default")
      (node (ref "IC2") (pin "38") (pinfunction "(S5:3/T7:1)PB23_38") (pintype "bidirectional"))
      (node (ref "R10") (pin "1") (pinfunction "1_1") (pintype "passive"))
    )
    (net (code "30") (name "D27_~{XB2_PWR}") (class "Default")
      (node (ref "IC2") (pin "19") (pinfunction "(S4:2/T5:0|0:4)PB10_19") (pintype "bidirectional"))
      (node (ref "R20") (pin "2") (pinfunction "2_2") (pintype "passive"))
      (node (ref "T3") (pin "1") (pinfunction "G_1") (pintype "passive"))
    )
    (net (code "31") (name "D28_CS_XB2") (class "Default")
      (node (ref "IC2") (pin "23") (pinfunction "(XIN/S2:2|4:2/T3:0|0:4)PA14_23") (pintype "bidirectional"))
      (node (ref "T1") (pin "4") (pinfunction "S_4") (pintype "passive"))
    )
    (net (code "32") (name "D29_INT_XB2") (class "Default")
      (node (ref "IC2") (pin "24") (pinfunction "(XOUT/S2:3|4:3/T3:1|0:5)PA15_24") (pintype "bidirectional"))
      (node (ref "R17") (pin "2") (pinfunction "2_2") (pintype "passive"))
    )
    (net (code "33") (name "D30_TX_XB2") (class "Default")
      (node (ref "IC2") (pin "15") (pinfunction "(S0:2|2:2/T1:0|0:2/AIN18)PA10_15") (pintype "bidirectional"))
      (node (ref "R9") (pin "1") (pinfunction "1_1") (pintype "passive"))
    )
    (net (code "34") (name "D31_RX_XB2") (class "Default")
      (node (ref "IC2") (pin "16") (pinfunction "(S0:3|2:3/T1:1|0:3/AIN19)PA11_16") (pintype "bidirectional"))
      (node (ref "R11") (pin "1") (pinfunction "1_1") (pintype "passive"))
    )
    (net (code "35") (name "GND") (class "Default")
      (node (ref "C1") (pin "1") (pinfunction "1_1") (pintype "passive"))
      (node (ref "C10") (pin "1") (pinfunction "1_1") (pintype "passive"))
      (node (ref "C11") (pin "1") (pinfunction "1_1") (pintype "passive"))
      (node (ref "C12") (pin "1") (pinfunction "1_1") (pintype "passive"))
      (node (ref "C13") (pin "1") (pinfunction "1_1") (pintype "passive"))
      (node (ref "C14") (pin "2") (pinfunction "2_2") (pintype "passive"))
      (node (ref "C15") (pin "1") (pinfunction "1_1") (pintype "passive"))
      (node (ref "C16") (pin "1") (pinfunction "1_1") (pintype "passive"))
      (node (ref "C17") (pin "1") (pinfunction "1_1") (pintype "passive"))
      (node (ref "C18") (pin "1") (pinfunction "1_1") (pintype "passive"))
      (node (ref "C19") (pin "1") (pinfunction "1_1") (pintype "passive"))
      (node (ref "C2") (pin "1") (pinfunction "1_1") (pintype "passive"))
      (node (ref "C20") (pin "1") (pinfunction "1_1") (pintype "passive"))
      (node (ref "C21") (pin "1") (pinfunction "1_1") (pintype "passive"))
      (node (ref "C22") (pin "1") (pinfunction "1_1") (pintype "passive"))
      (node (ref "C23") (pin "1") (pinfunction "1_1") (pintype "passive"))
      (node (ref "C24") (pin "1") (pinfunction "1_1") (pintype "passive"))
      (node (ref "C25") (pin "1") (pinfunction "1_1") (pintype "passive"))
      (node (ref "C26") (pin "1") (pinfunction "1_1") (pintype "passive"))
      (node (ref "C27") (pin "1") (pinfunction "1_1") (pintype "passive"))
      (node (ref "C3") (pin "1") (pinfunction "1_1") (pintype "passive"))
      (node (ref "C4") (pin "1") (pinfunction "1_1") (pintype "passive"))
      (node (ref "C5") (pin "1") (pinfunction "1_1") (pintype "passive"))
      (node (ref "C6") (pin "1") (pinfunction "1_1") (pintype "passive"))
      (node (ref "C7") (pin "1") (pinfunction "1_1") (pintype "passive"))
      (node (ref "C8") (pin "1") (pinfunction "1_1") (pintype "passive"))
      (node (ref "C9") (pin "1") (pinfunction "1_1") (pintype "passive"))
      (node (ref "D10") (pin "1") (pinfunction "A_1") (pintype "passive"))
      (node (ref "D11") (pin "1") (pinfunction "A_1") (pintype "passive"))
      (node (ref "D12") (pin "1") (pinfunction "A_1") (pintype "passive"))
      (node (ref "D13") (pin "1") (pinfunction "A_1") (pintype "passive"))
      (node (ref "D14") (pin "1") (pinfunction "A_1") (pintype "passive"))
      (node (ref "D15") (pin "1") (pinfunction "A_1") (pintype "passive"))
      (node (ref "D16") (pin "C") (pinfunction "C_C") (pintype "passive"))
      (node (ref "D17") (pin "1") (pinfunction "A_1") (pintype "passive"))
      (node (ref "D18") (pin "1") (pinfunction "A_1") (pintype "passive"))
      (node (ref "D19") (pin "1") (pinfunction "A_1") (pintype "passive"))
      (node (ref "D2") (pin "C") (pinfunction "C_C") (pintype "passive"))
      (node (ref "D20") (pin "C") (pinfunction "C_C") (pintype "passive"))
      (node (ref "D3") (pin "C") (pinfunction "C_C") (pintype "passive"))
      (node (ref "D4") (pin "A") (pinfunction "A_A") (pintype "passive"))
      (node (ref "D5") (pin "3") (pinfunction "A_3") (pintype "passive"))
      (node (ref "D6") (pin "A") (pinfunction "A_A") (pintype "passive"))
      (node (ref "D7") (pin "C") (pinfunction "C_C") (pintype "passive"))
      (node (ref "D8") (pin "C") (pinfunction "C_C") (pintype "passive"))
      (node (ref "D9") (pin "1") (pinfunction "A_1") (pintype "passive"))
      (node (ref "IC1") (pin "1") (pinfunction "GND_1") (pintype "power_in"))
      (node (ref "IC2") (pin "18") (pinfunction "GND_18") (pintype "power_in"))
      (node (ref "IC2") (pin "35") (pinfunction "GND_35") (pintype "power_in"))
      (node (ref "IC2") (pin "42") (pinfunction "GND_42") (pintype "power_in"))
      (node (ref "IC2") (pin "5") (pinfunction "GND_5") (pintype "power_in"))
      (node (ref "IC2") (pin "TP") (pinfunction "GND_TP") (pintype "power_in"))
      (node (ref "IC3") (pin "1") (pinfunction "GND_1") (pintype "power_in"))
      (node (ref "IC4") (pin "1") (pinfunction "GND_1") (pintype "power_in"))
      (node (ref "IC5") (pin "10") (pinfunction "GND_10") (pintype "power_in"))
      (node (ref "IC6") (pin "4") (pinfunction "GNDA_4") (pintype "power_in"))
      (node (ref "IC6") (pin "6") (pinfunction "GND_6") (pintype "power_in"))
      (node (ref "IC7") (pin "4") (pinfunction "GND_4") (pintype "power_in"))
      (node (ref "J1") (pin "GND") (pinfunction "GND_GND") (pintype "power_in"))
      (node (ref "J10") (pin "1") (pinfunction "1_1") (pintype "passive"))
      (node (ref "J11") (pin "1") (pinfunction "1_1") (pintype "passive"))
      (node (ref "J12") (pin "1") (pinfunction "1_1") (pintype "passive"))
      (node (ref "J13") (pin "1") (pinfunction "1_1") (pintype "passive"))
      (node (ref "J14") (pin "1") (pinfunction "1_1") (pintype "passive"))
      (node (ref "J15") (pin "3") (pinfunction "3_3") (pintype "passive"))
      (node (ref "J2") (pin "2") (pinfunction "2_2") (pintype "passive"))
      (node (ref "J3") (pin "GND@1") (pinfunction "GND_GND@1") (pintype "power_in"))
      (node (ref "J3") (pin "GND@2") (pinfunction "GND_GND@2") (pintype "power_in"))
      (node (ref "J3") (pin "GND@3") (pinfunction "GND_GND@3") (pintype "power_in"))
      (node (ref "J4") (pin "1") (pinfunction "1_1") (pintype "passive"))
      (node (ref "J5") (pin "1") (pinfunction "1_1") (pintype "passive"))
      (node (ref "J6") (pin "1") (pinfunction "1_1") (pintype "passive"))
      (node (ref "J7") (pin "1") (pinfunction "1_1") (pintype "passive"))
      (node (ref "J8") (pin "1") (pinfunction "1_1") (pintype "passive"))
      (node (ref "J9") (pin "1") (pinfunction "1_1") (pintype "passive"))
      (node (ref "R1") (pin "1") (pinfunction "1_1") (pintype "passive"))
      (node (ref "R19") (pin "2") (pinfunction "2_2") (pintype "passive"))
      (node (ref "R21") (pin "2") (pinfunction "2_2") (pintype "passive"))
      (node (ref "R32") (pin "2") (pinfunction "2_2") (pintype "passive"))
      (node (ref "R37") (pin "2") (pinfunction "2_2") (pintype "passive"))
      (node (ref "SW1") (pin "3") (pinfunction "S1_3") (pintype "passive"))
      (node (ref "SW1") (pin "4") (pinfunction "S1_4") (pintype "passive"))
      (node (ref "SW2") (pin "1") (pinfunction "P1_1") (pintype "passive"))
      (node (ref "SW2") (pin "2") (pinfunction "P1_2") (pintype "passive"))
      (node (ref "T5") (pin "1") (pinfunction "S_1") (pintype "passive"))
      (node (ref "T5") (pin "4") (pinfunction "S_4") (pintype "passive"))
      (node (ref "XBEE1") (pin "10") (pinfunction "GND_10") (pintype "power_in"))
      (node (ref "XBEE2") (pin "10") (pinfunction "GND_10") (pintype "power_in"))
    )
    (net (code "36") (name "I2C_SCL") (class "Default")
      (node (ref "J10") (pin "4") (pinfunction "4_4") (pintype "passive"))
      (node (ref "J11") (pin "4") (pinfunction "4_4") (pintype "passive"))
      (node (ref "J12") (pin "4") (pinfunction "4_4") (pintype "passive"))
      (node (ref "J13") (pin "4") (pinfunction "4_4") (pintype "passive"))
      (node (ref "J9") (pin "4") (pinfunction "4_4") (pintype "passive"))
      (node (ref "R41") (pin "1") (pinfunction "1_1") (pintype "passive"))
      (node (ref "T6") (pin "6") (pinfunction "D_6") (pintype "passive"))
    )
    (net (code "37") (name "I2C_SDA") (class "Default")
      (node (ref "J10") (pin "3") (pinfunction "3_3") (pintype "passive"))
      (node (ref "J11") (pin "3") (pinfunction "3_3") (pintype "passive"))
      (node (ref "J12") (pin "3") (pinfunction "3_3") (pintype "passive"))
      (node (ref "J13") (pin "3") (pinfunction "3_3") (pintype "passive"))
      (node (ref "J9") (pin "3") (pinfunction "3_3") (pintype "passive"))
      (node (ref "R42") (pin "1") (pinfunction "1_1") (pintype "passive"))
      (node (ref "T6") (pin "3") (pinfunction "D_3") (pintype "passive"))
    )
    (net (code "38") (name "I2C_VCC") (class "Default")
      (node (ref "C24") (pin "2") (pinfunction "2_2") (pintype "passive"))
      (node (ref "J10") (pin "2") (pinfunction "2_2") (pintype "passive"))
      (node (ref "J11") (pin "2") (pinfunction "2_2") (pintype "passive"))
      (node (ref "J12") (pin "2") (pinfunction "2_2") (pintype "passive"))
      (node (ref "J13") (pin "2") (pinfunction "2_2") (pintype "passive"))
      (node (ref "J9") (pin "2") (pinfunction "2_2") (pintype "passive"))
      (node (ref "R41") (pin "2") (pinfunction "2_2") (pintype "passive"))
      (node (ref "R42") (pin "2") (pinfunction "2_2") (pintype "passive"))
      (node (ref "R43") (pin "2") (pinfunction "2_2") (pintype "passive"))
      (node (ref "T7") (pin "3") (pinfunction "D_3") (pintype "passive"))
    )
    (net (code "39") (name "IO1") (class "Default")
      (node (ref "J5") (pin "3") (pinfunction "3_3") (pintype "passive"))
      (node (ref "R31") (pin "2") (pinfunction "2_2") (pintype "passive"))
    )
    (net (code "40") (name "IO2") (class "Default")
      (node (ref "J5") (pin "4") (pinfunction "4_4") (pintype "passive"))
      (node (ref "R30") (pin "2") (pinfunction "2_2") (pintype "passive"))
    )
    (net (code "41") (name "IO3") (class "Default")
      (node (ref "J6") (pin "3") (pinfunction "3_3") (pintype "passive"))
      (node (ref "R29") (pin "2") (pinfunction "2_2") (pintype "passive"))
    )
    (net (code "42") (name "IO4") (class "Default")
      (node (ref "J6") (pin "4") (pinfunction "4_4") (pintype "passive"))
      (node (ref "R28") (pin "2") (pinfunction "2_2") (pintype "passive"))
    )
    (net (code "43") (name "IO5") (class "Default")
      (node (ref "J8") (pin "3") (pinfunction "3_3") (pintype "passive"))
      (node (ref "R27") (pin "2") (pinfunction "2_2") (pintype "passive"))
    )
    (net (code "44") (name "IO6") (class "Default")
      (node (ref "J8") (pin "4") (pinfunction "4_4") (pintype "passive"))
      (node (ref "R26") (pin "2") (pinfunction "2_2") (pintype "passive"))
    )
    (net (code "45") (name "Net-(D1-PadA)") (class "Default")
      (node (ref "D1") (pin "A") (pinfunction "A_A") (pintype "passive"))
      (node (ref "J2") (pin "1") (pinfunction "1_1") (pintype "passive"))
    )
    (net (code "46") (name "Net-(D1-PadC)") (class "Default")
      (node (ref "D1") (pin "C") (pinfunction "C_C") (pintype "passive"))
      (node (ref "F2") (pin "1") (pinfunction "1_1") (pintype "passive"))
    )
    (net (code "47") (name "Net-(D2-PadA)") (class "Default")
      (node (ref "D2") (pin "A") (pinfunction "A_A") (pintype "passive"))
      (node (ref "R3") (pin "2") (pinfunction "2_2") (pintype "passive"))
    )
    (net (code "48") (name "Net-(D3-PadA)") (class "Default")
      (node (ref "D3") (pin "A") (pinfunction "A_A") (pintype "passive"))
      (node (ref "R4") (pin "2") (pinfunction "2_2") (pintype "passive"))
    )
    (net (code "49") (name "Net-(D7-PadA)") (class "Default")
      (node (ref "D7") (pin "A") (pinfunction "A_A") (pintype "passive"))
      (node (ref "R22") (pin "1") (pinfunction "1_1") (pintype "passive"))
    )
    (net (code "50") (name "Net-(D8-PadA)") (class "Default")
      (node (ref "D8") (pin "A") (pinfunction "A_A") (pintype "passive"))
      (node (ref "R23") (pin "1") (pinfunction "1_1") (pintype "passive"))
    )
    (net (code "51") (name "Net-(D16-PadA)") (class "Default")
      (node (ref "D16") (pin "A") (pinfunction "A_A") (pintype "passive"))
      (node (ref "R34") (pin "1") (pinfunction "1_1") (pintype "passive"))
    )
    (net (code "52") (name "Net-(D20-PadA)") (class "Default")
      (node (ref "D20") (pin "A") (pinfunction "A_A") (pintype "passive"))
      (node (ref "R43") (pin "1") (pinfunction "1_1") (pintype "passive"))
    )
    (net (code "53") (name "Net-(F1-Pad1)") (class "Default")
      (node (ref "F1") (pin "1") (pinfunction "1_1") (pintype "passive"))
      (node (ref "J1") (pin "VBUS") (pinfunction "VBUS_VBUS") (pintype "power_in"))
    )
    (net (code "54") (name "Net-(IC2-(XIN32{slash}S1:0{slash}T2:0)PA00)") (class "Default")
      (node (ref "C14") (pin "1") (pinfunction "1_1") (pintype "passive"))
      (node (ref "IC2") (pin "1") (pinfunction "(XIN32/S1:0/T2:0)PA00_1") (pintype "bidirectional"))
      (node (ref "Q1") (pin "2") (pinfunction "2_2") (pintype "passive"))
    )
    (net (code "55") (name "Net-(IC2-(XOUT32{slash}S1:1{slash}T2:1)PA01)") (class "Default")
      (node (ref "C15") (pin "2") (pinfunction "2_2") (pintype "passive"))
      (node (ref "IC2") (pin "2") (pinfunction "(XOUT32/S1:1/T2:1)PA01_2") (pintype "bidirectional"))
      (node (ref "Q1") (pin "1") (pinfunction "1_1") (pintype "passive"))
    )
    (net (code "56") (name "Net-(IC2-VCCANA)") (class "Default")
      (node (ref "C10") (pin "2") (pinfunction "2_2") (pintype "passive"))
      (node (ref "C11") (pin "2") (pinfunction "2_2") (pintype "passive"))
      (node (ref "C8") (pin "2") (pinfunction "2_2") (pintype "passive"))
      (node (ref "IC2") (pin "6") (pinfunction "VCCANA_6") (pintype "power_in"))
      (node (ref "L1") (pin "2") (pinfunction "2_2") (pintype "passive"))
    )
    (net (code "57") (name "Net-(IC2-VCCCORE)") (class "Default")
      (node (ref "C13") (pin "2") (pinfunction "2_2") (pintype "passive"))
      (node (ref "IC2") (pin "43") (pinfunction "VCCCORE_43") (pintype "power_in"))
    )
    (net (code "58") (name "Net-(IC3-RST)") (class "Default")
      (node (ref "IC3") (pin "2") (pinfunction "RST_2") (pintype "output"))
      (node (ref "XBEE2") (pin "5") (pinfunction "~{RESET}_5") (pintype "bidirectional"))
    )
    (net (code "59") (name "Net-(IC4-RST)") (class "Default")
      (node (ref "IC4") (pin "2") (pinfunction "RST_2") (pintype "output"))
      (node (ref "XBEE1") (pin "5") (pinfunction "~{RESET}_5") (pintype "bidirectional"))
    )
    (net (code "60") (name "Net-(IC5A-A1)") (class "Default")
      (node (ref "IC5") (pin "1") (pinfunction "G_1") (pintype "input"))
      (node (ref "IC5") (pin "2") (pinfunction "A1_2") (pintype "input"))
      (node (ref "R12") (pin "1") (pinfunction "1_1") (pintype "passive"))
      (node (ref "T1") (pin "6") (pinfunction "D_6") (pintype "passive"))
    )
    (net (code "61") (name "Net-(IC5B-A4)") (class "Default")
      (node (ref "IC5") (pin "17") (pinfunction "A4_17") (pintype "input"))
      (node (ref "IC5") (pin "19") (pinfunction "G_19") (pintype "input"))
      (node (ref "R13") (pin "1") (pinfunction "1_1") (pintype "passive"))
      (node (ref "T1") (pin "3") (pinfunction "D_3") (pintype "passive"))
    )
    (net (code "62") (name "Net-(IC6-SDO1)") (class "Default")
      (node (ref "IC6") (pin "17") (pinfunction "SDO1_17") (pintype "bidirectional"))
      (node (ref "J15") (pin "2") (pinfunction "2_2") (pintype "passive"))
    )
    (net (code "63") (name "Net-(IC6-SDO2)") (class "Default")
      (node (ref "IC6") (pin "12") (pinfunction "SDO2_12") (pintype "bidirectional"))
      (node (ref "J14") (pin "2") (pinfunction "2_2") (pintype "passive"))
    )
    (net (code "64") (name "Net-(J1-SHIELD-PadSHLD1)") (class "Default")
      (node (ref "J1") (pin "SHLD1") (pinfunction "SHIELD_SHLD1") (pintype "passive"))
      (node (ref "J1") (pin "SHLD2") (pinfunction "SHIELD_SHLD2") (pintype "passive"))
      (node (ref "J1") (pin "SHLD3") (pinfunction "SHIELD_SHLD3") (pintype "passive"))
      (node (ref "J1") (pin "SHLD4") (pinfunction "SHIELD_SHLD4") (pintype "passive"))
      (node (ref "J1") (pin "SHLD5") (pinfunction "SHIELD_SHLD5") (pintype "passive"))
      (node (ref "J1") (pin "SHLD6") (pinfunction "SHIELD_SHLD6") (pintype "passive"))
      (node (ref "J1") (pin "SHLD7") (pinfunction "SHIELD_SHLD7") (pintype "passive"))
      (node (ref "J1") (pin "SHLD8") (pinfunction "SHIELD_SHLD8") (pintype "passive"))
      (node (ref "R1") (pin "2") (pinfunction "2_2") (pintype "passive"))
    )
    (net (code "65") (name "Net-(J4-Pad3)") (class "Default")
      (node (ref "J4") (pin "3") (pinfunction "3_3") (pintype "passive"))
      (node (ref "R25") (pin "2") (pinfunction "2_2") (pintype "passive"))
    )
    (net (code "66") (name "Net-(J4-Pad4)") (class "Default")
      (node (ref "J4") (pin "4") (pinfunction "4_4") (pintype "passive"))
      (node (ref "R24") (pin "2") (pinfunction "2_2") (pintype "passive"))
    )
    (net (code "67") (name "Net-(J7-Pad3)") (class "Default")
      (node (ref "J7") (pin "3") (pinfunction "3_3") (pintype "passive"))
      (node (ref "R36") (pin "2") (pinfunction "2_2") (pintype "passive"))
    )
    (net (code "68") (name "Net-(J7-Pad4)") (class "Default")
      (node (ref "J7") (pin "4") (pinfunction "4_4") (pintype "passive"))
      (node (ref "R35") (pin "2") (pinfunction "2_2") (pintype "passive"))
    )
    (net (code "69") (name "Net-(R2-Pad2)") (class "Default")
      (node (ref "R2") (pin "2") (pinfunction "2_2") (pintype "passive"))
      (node (ref "SW1") (pin "1") (pinfunction "P1_1") (pintype "passive"))
      (node (ref "SW1") (pin "2") (pinfunction "P1_2") (pintype "passive"))
    )
    (net (code "70") (name "Net-(R6-Pad2)") (class "Default")
      (node (ref "R6") (pin "2") (pinfunction "2_2") (pintype "passive"))
      (node (ref "SW2") (pin "3") (pinfunction "S1_3") (pintype "passive"))
      (node (ref "SW2") (pin "4") (pinfunction "S1_4") (pintype "passive"))
    )
    (net (code "71") (name "Net-(T4-G)") (class "Default")
      (node (ref "R33") (pin "2") (pinfunction "2_2") (pintype "passive"))
      (node (ref "T4") (pin "1") (pinfunction "G_1") (pintype "passive"))
      (node (ref "T5") (pin "3") (pinfunction "D_3") (pintype "passive"))
    )
    (net (code "72") (name "Net-(T5A-D)") (class "Default")
      (node (ref "R40") (pin "2") (pinfunction "2_2") (pintype "passive"))
      (node (ref "T5") (pin "6") (pinfunction "D_6") (pintype "passive"))
      (node (ref "T7") (pin "1") (pinfunction "G_1") (pintype "passive"))
    )
    (net (code "73") (name "Net-(XBEE1-DIN{slash}RX{slash}~{CFG})") (class "Default")
      (node (ref "R8") (pin "2") (pinfunction "2_2") (pintype "passive"))
      (node (ref "XBEE1") (pin "3") (pinfunction "DIN/RX/~{CFG}_3") (pintype "bidirectional"))
    )
    (net (code "74") (name "Net-(XBEE1-DIO7{slash}CTS)") (class "Default")
      (node (ref "R15") (pin "1") (pinfunction "1_1") (pintype "passive"))
      (node (ref "XBEE1") (pin "12") (pinfunction "DIO7/CTS_12") (pintype "bidirectional"))
    )
    (net (code "75") (name "Net-(XBEE1-DOUT{slash}TX)") (class "Default")
      (node (ref "R10") (pin "2") (pinfunction "2_2") (pintype "passive"))
      (node (ref "XBEE1") (pin "2") (pinfunction "DOUT/TX_2") (pintype "bidirectional"))
    )
    (net (code "76") (name "Net-(XBEE2-DIN{slash}RX{slash}~{CFG})") (class "Default")
      (node (ref "R9") (pin "2") (pinfunction "2_2") (pintype "passive"))
      (node (ref "XBEE2") (pin "3") (pinfunction "DIN/RX/~{CFG}_3") (pintype "bidirectional"))
    )
    (net (code "77") (name "Net-(XBEE2-DIO7{slash}CTS)") (class "Default")
      (node (ref "R17") (pin "1") (pinfunction "1_1") (pintype "passive"))
      (node (ref "XBEE2") (pin "12") (pinfunction "DIO7/CTS_12") (pintype "bidirectional"))
    )
    (net (code "78") (name "Net-(XBEE2-DOUT{slash}TX)") (class "Default")
      (node (ref "R11") (pin "2") (pinfunction "2_2") (pintype "passive"))
      (node (ref "XBEE2") (pin "2") (pinfunction "DOUT/TX_2") (pintype "bidirectional"))
    )
    (net (code "79") (name "RST") (class "Default")
      (node (ref "C12") (pin "2") (pinfunction "2_2") (pintype "passive"))
      (node (ref "IC2") (pin "40") (pinfunction "~{RESET}_40") (pintype "input"))
      (node (ref "J3") (pin "RST") (pinfunction "RST_RST") (pintype "bidirectional"))
      (node (ref "R6") (pin "1") (pinfunction "1_1") (pintype "passive"))
      (node (ref "R7") (pin "2") (pinfunction "2_2") (pintype "passive"))
    )
    (net (code "80") (name "SWCLK") (class "Default")
      (node (ref "IC2") (pin "45") (pinfunction "(SWCLK/S1:2/T1:0)PA30_45") (pintype "bidirectional"))
      (node (ref "J3") (pin "SWCLK") (pinfunction "SWCLK_SWCLK") (pintype "bidirectional"))
      (node (ref "R5") (pin "2") (pinfunction "2_2") (pintype "passive"))
    )
    (net (code "81") (name "SWDIO") (class "Default")
      (node (ref "IC2") (pin "46") (pinfunction "(SWDIO/S1:3/T1:1)PA31_46") (pintype "bidirectional"))
      (node (ref "J3") (pin "SWDIO") (pinfunction "SWDIO_SWDIO") (pintype "bidirectional"))
    )
    (net (code "82") (name "UART_VCC") (class "Default")
      (node (ref "C23") (pin "2") (pinfunction "2_2") (pintype "passive"))
      (node (ref "J4") (pin "2") (pinfunction "2_2") (pintype "passive"))
      (node (ref "J7") (pin "2") (pinfunction "2_2") (pintype "passive"))
      (node (ref "R34") (pin "2") (pinfunction "2_2") (pintype "passive"))
      (node (ref "T4") (pin "3") (pinfunction "D_3") (pintype "passive"))
    )
    (net (code "83") (name "USB_D_N") (class "Default")
      (node (ref "D5") (pin "1") (pinfunction "C1_1") (pintype "passive"))
      (node (ref "IC2") (pin "33") (pinfunction "(USBM/S3:2|5:2/T5:0|1:2)PA24_33") (pintype "bidirectional"))
      (node (ref "J1") (pin "D-") (pinfunction "D-_D-") (pintype "bidirectional"))
    )
    (net (code "84") (name "USB_D_P") (class "Default")
      (node (ref "D5") (pin "2") (pinfunction "C2_2") (pintype "passive"))
      (node (ref "IC2") (pin "34") (pinfunction "(USBP/S3:3|5:3/T5:1|1:3)PA25_34") (pintype "bidirectional"))
      (node (ref "J1") (pin "D+") (pinfunction "D+_D+") (pintype "bidirectional"))
    )
    (net (code "85") (name "XB1_CS") (class "Default")
      (node (ref "IC5") (pin "18") (pinfunction "Y1_18") (pintype "tri_state"))
      (node (ref "R14") (pin "1") (pinfunction "1_1") (pintype "passive"))
      (node (ref "XBEE1") (pin "17") (pinfunction "AD3/DIO3/SS_17") (pintype "bidirectional"))
    )
    (net (code "86") (name "XB1_MISO") (class "Default")
      (node (ref "IC5") (pin "8") (pinfunction "A4_8") (pintype "input"))
      (node (ref "XBEE1") (pin "4") (pinfunction "MISO/DIO12_4") (pintype "bidirectional"))
    )
    (net (code "87") (name "XB1_MOSI") (class "Default")
      (node (ref "IC5") (pin "16") (pinfunction "Y2_16") (pintype "tri_state"))
      (node (ref "XBEE1") (pin "11") (pinfunction "DIO4/MOSI_11") (pintype "bidirectional"))
    )
    (net (code "88") (name "XB1_SCK") (class "Default")
      (node (ref "IC5") (pin "14") (pinfunction "Y3_14") (pintype "tri_state"))
      (node (ref "XBEE1") (pin "18") (pinfunction "AD2/DIO2/SCK_18") (pintype "bidirectional"))
    )
    (net (code "89") (name "XB1_VCC") (class "Default")
      (node (ref "C16") (pin "2") (pinfunction "2_2") (pintype "passive"))
      (node (ref "C18") (pin "2") (pinfunction "2_2") (pintype "passive"))
      (node (ref "C20") (pin "2") (pinfunction "2_2") (pintype "passive"))
      (node (ref "IC4") (pin "3") (pinfunction "VCC_3") (pintype "power_in"))
      (node (ref "R14") (pin "2") (pinfunction "2_2") (pintype "passive"))
      (node (ref "R19") (pin "1") (pinfunction "1_1") (pintype "passive"))
      (node (ref "R22") (pin "2") (pinfunction "2_2") (pintype "passive"))
      (node (ref "T1") (pin "2") (pinfunction "G_2") (pintype "passive"))
      (node (ref "T2") (pin "3") (pinfunction "D_3") (pintype "passive"))
      (node (ref "XBEE1") (pin "1") (pinfunction "VCC_1") (pintype "power_in"))
    )
    (net (code "90") (name "XB2_CS") (class "Default")
      (node (ref "IC5") (pin "3") (pinfunction "Y4_3") (pintype "tri_state"))
      (node (ref "R16") (pin "1") (pinfunction "1_1") (pintype "passive"))
      (node (ref "XBEE2") (pin "17") (pinfunction "AD3/DIO3/SS_17") (pintype "bidirectional"))
    )
    (net (code "91") (name "XB2_MISO") (class "Default")
      (node (ref "IC5") (pin "11") (pinfunction "A1_11") (pintype "input"))
      (node (ref "XBEE2") (pin "4") (pinfunction "MISO/DIO12_4") (pintype "bidirectional"))
    )
    (net (code "92") (name "XB2_MOSI") (class "Default")
      (node (ref "IC5") (pin "7") (pinfunction "Y2_7") (pintype "tri_state"))
      (node (ref "XBEE2") (pin "11") (pinfunction "DIO4/MOSI_11") (pintype "bidirectional"))
    )
    (net (code "93") (name "XB2_SCK") (class "Default")
      (node (ref "IC5") (pin "5") (pinfunction "Y3_5") (pintype "tri_state"))
      (node (ref "XBEE2") (pin "18") (pinfunction "AD2/DIO2/SCK_18") (pintype "bidirectional"))
    )
    (net (code "94") (name "XB2_VCC") (class "Default")
      (node (ref "C17") (pin "2") (pinfunction "2_2") (pintype "passive"))
      (node (ref "C19") (pin "2") (pinfunction "2_2") (pintype "passive"))
      (node (ref "C21") (pin "2") (pinfunction "2_2") (pintype "passive"))
      (node (ref "IC3") (pin "3") (pinfunction "VCC_3") (pintype "power_in"))
      (node (ref "R16") (pin "2") (pinfunction "2_2") (pintype "passive"))
      (node (ref "R21") (pin "1") (pinfunction "1_1") (pintype "passive"))
      (node (ref "R23") (pin "2") (pinfunction "2_2") (pintype "passive"))
      (node (ref "T1") (pin "5") (pinfunction "G_5") (pintype "passive"))
      (node (ref "T3") (pin "3") (pinfunction "D_3") (pintype "passive"))
      (node (ref "XBEE2") (pin "1") (pinfunction "VCC_1") (pintype "power_in"))
    )
    (net (code "95") (name "unconnected-(IC6-CSB1-Pad16)") (class "Default")
      (node (ref "IC6") (pin "16") (pinfunction "CSB1_16") (pintype "bidirectional"))
    )
    (net (code "96") (name "unconnected-(IC6-CSB2-Pad5)") (class "Default")
      (node (ref "IC6") (pin "5") (pinfunction "CSB2_5") (pintype "bidirectional"))
    )
    (net (code "97") (name "unconnected-(IC6-CSB3-Pad20)") (class "Default")
      (node (ref "IC6") (pin "20") (pinfunction "CSB3_20") (pintype "bidirectional"))
    )
    (net (code "98") (name "unconnected-(IC6-DRDYM-Pad2)") (class "Default")
      (node (ref "IC6") (pin "2") (pinfunction "DRDYM_2") (pintype "bidirectional"))
    )
    (net (code "99") (name "unconnected-(IC6-INT1-Pad19)") (class "Default")
      (node (ref "IC6") (pin "19") (pinfunction "INT1_19") (pintype "output"))
    )
    (net (code "100") (name "unconnected-(IC6-INT2-Pad1)") (class "Default")
      (node (ref "IC6") (pin "1") (pinfunction "INT2_1") (pintype "output"))
    )
    (net (code "101") (name "unconnected-(IC6-INT3-Pad14)") (class "Default")
      (node (ref "IC6") (pin "14") (pinfunction "INT3_14") (pintype "output"))
    )
    (net (code "102") (name "unconnected-(IC6-INT4-Pad15)") (class "Default")
      (node (ref "IC6") (pin "15") (pinfunction "INT4_15") (pintype "output"))
    )
    (net (code "103") (name "unconnected-(IC6-INT5-Pad10)") (class "Default")
      (node (ref "IC6") (pin "10") (pinfunction "INT5_10") (pintype "bidirectional"))
    )
    (net (code "104") (name "unconnected-(XBEE1-AD0{slash}DIO0{slash}SDA{slash}CB-Pad20)") (class "Default")
      (node (ref "XBEE1") (pin "20") (pinfunction "AD0/DIO0/SDA/CB_20") (pintype "bidirectional"))
    )
    (net (code "105") (name "unconnected-(XBEE1-AD1{slash}DIO1{slash}SCL{slash}ATTN-Pad19)") (class "Default")
      (node (ref "XBEE1") (pin "19") (pinfunction "AD1/DIO1/SCL/ATTN_19") (pintype "bidirectional"))
    )
    (net (code "106") (name "unconnected-(XBEE1-DIO5{slash}ASSC-Pad15)") (class "Default")
      (node (ref "XBEE1") (pin "15") (pinfunction "DIO5/ASSC_15") (pintype "bidirectional"))
    )
    (net (code "107") (name "unconnected-(XBEE1-DIO6{slash}RTS-Pad16)") (class "Default")
      (node (ref "XBEE1") (pin "16") (pinfunction "DIO6/RTS_16") (pintype "bidirectional"))
    )
    (net (code "108") (name "unconnected-(XBEE1-DIO9{slash}ON_~{SLEEP}-Pad13)") (class "Default")
      (node (ref "XBEE1") (pin "13") (pinfunction "DIO9/ON_~{SLEEP}_13") (pintype "bidirectional"))
    )
    (net (code "109") (name "unconnected-(XBEE1-DTR{slash}DIO8-Pad9)") (class "Default")
      (node (ref "XBEE1") (pin "9") (pinfunction "DTR/DIO8_9") (pintype "bidirectional"))
    )
    (net (code "110") (name "unconnected-(XBEE1-PWM1{slash}DIO11-Pad7)") (class "Default")
      (node (ref "XBEE1") (pin "7") (pinfunction "PWM1/DIO11_7") (pintype "bidirectional"))
    )
    (net (code "111") (name "unconnected-(XBEE1-RES-Pad8)") (class "Default")
      (node (ref "XBEE1") (pin "8") (pinfunction "RES_8") (pintype "bidirectional"))
    )
    (net (code "112") (name "unconnected-(XBEE1-RSSI{slash}PWM0{slash}DIO10-Pad6)") (class "Default")
      (node (ref "XBEE1") (pin "6") (pinfunction "RSSI/PWM0/DIO10_6") (pintype "bidirectional"))
    )
    (net (code "113") (name "unconnected-(XBEE1-VREF-Pad14)") (class "Default")
      (node (ref "XBEE1") (pin "14") (pinfunction "VREF_14") (pintype "bidirectional"))
    )
    (net (code "114") (name "unconnected-(XBEE2-AD0{slash}DIO0{slash}SDA{slash}CB-Pad20)") (class "Default")
      (node (ref "XBEE2") (pin "20") (pinfunction "AD0/DIO0/SDA/CB_20") (pintype "bidirectional"))
    )
    (net (code "115") (name "unconnected-(XBEE2-AD1{slash}DIO1{slash}SCL{slash}ATTN-Pad19)") (class "Default")
      (node (ref "XBEE2") (pin "19") (pinfunction "AD1/DIO1/SCL/ATTN_19") (pintype "bidirectional"))
    )
    (net (code "116") (name "unconnected-(XBEE2-DIO5{slash}ASSC-Pad15)") (class "Default")
      (node (ref "XBEE2") (pin "15") (pinfunction "DIO5/ASSC_15") (pintype "bidirectional"))
    )
    (net (code "117") (name "unconnected-(XBEE2-DIO6{slash}RTS-Pad16)") (class "Default")
      (node (ref "XBEE2") (pin "16") (pinfunction "DIO6/RTS_16") (pintype "bidirectional"))
    )
    (net (code "118") (name "unconnected-(XBEE2-DIO9{slash}ON_~{SLEEP}-Pad13)") (class "Default")
      (node (ref "XBEE2") (pin "13") (pinfunction "DIO9/ON_~{SLEEP}_13") (pintype "bidirectional"))
    )
    (net (code "119") (name "unconnected-(XBEE2-DTR{slash}DIO8-Pad9)") (class "Default")
      (node (ref "XBEE2") (pin "9") (pinfunction "DTR/DIO8_9") (pintype "bidirectional"))
    )
    (net (code "120") (name "unconnected-(XBEE2-PWM1{slash}DIO11-Pad7)") (class "Default")
      (node (ref "XBEE2") (pin "7") (pinfunction "PWM1/DIO11_7") (pintype "bidirectional"))
    )
    (net (code "121") (name "unconnected-(XBEE2-RES-Pad8)") (class "Default")
      (node (ref "XBEE2") (pin "8") (pinfunction "RES_8") (pintype "bidirectional"))
    )
    (net (code "122") (name "unconnected-(XBEE2-RSSI{slash}PWM0{slash}DIO10-Pad6)") (class "Default")
      (node (ref "XBEE2") (pin "6") (pinfunction "RSSI/PWM0/DIO10_6") (pintype "bidirectional"))
    )
    (net (code "123") (name "unconnected-(XBEE2-VREF-Pad14)") (class "Default")
      (node (ref "XBEE2") (pin "14") (pinfunction "VREF_14") (pintype "bidirectional"))
    )
  )
)
